# mcat-4cu-b-v2f.net
KiCad netlist of a schematic drawn in EAGLE
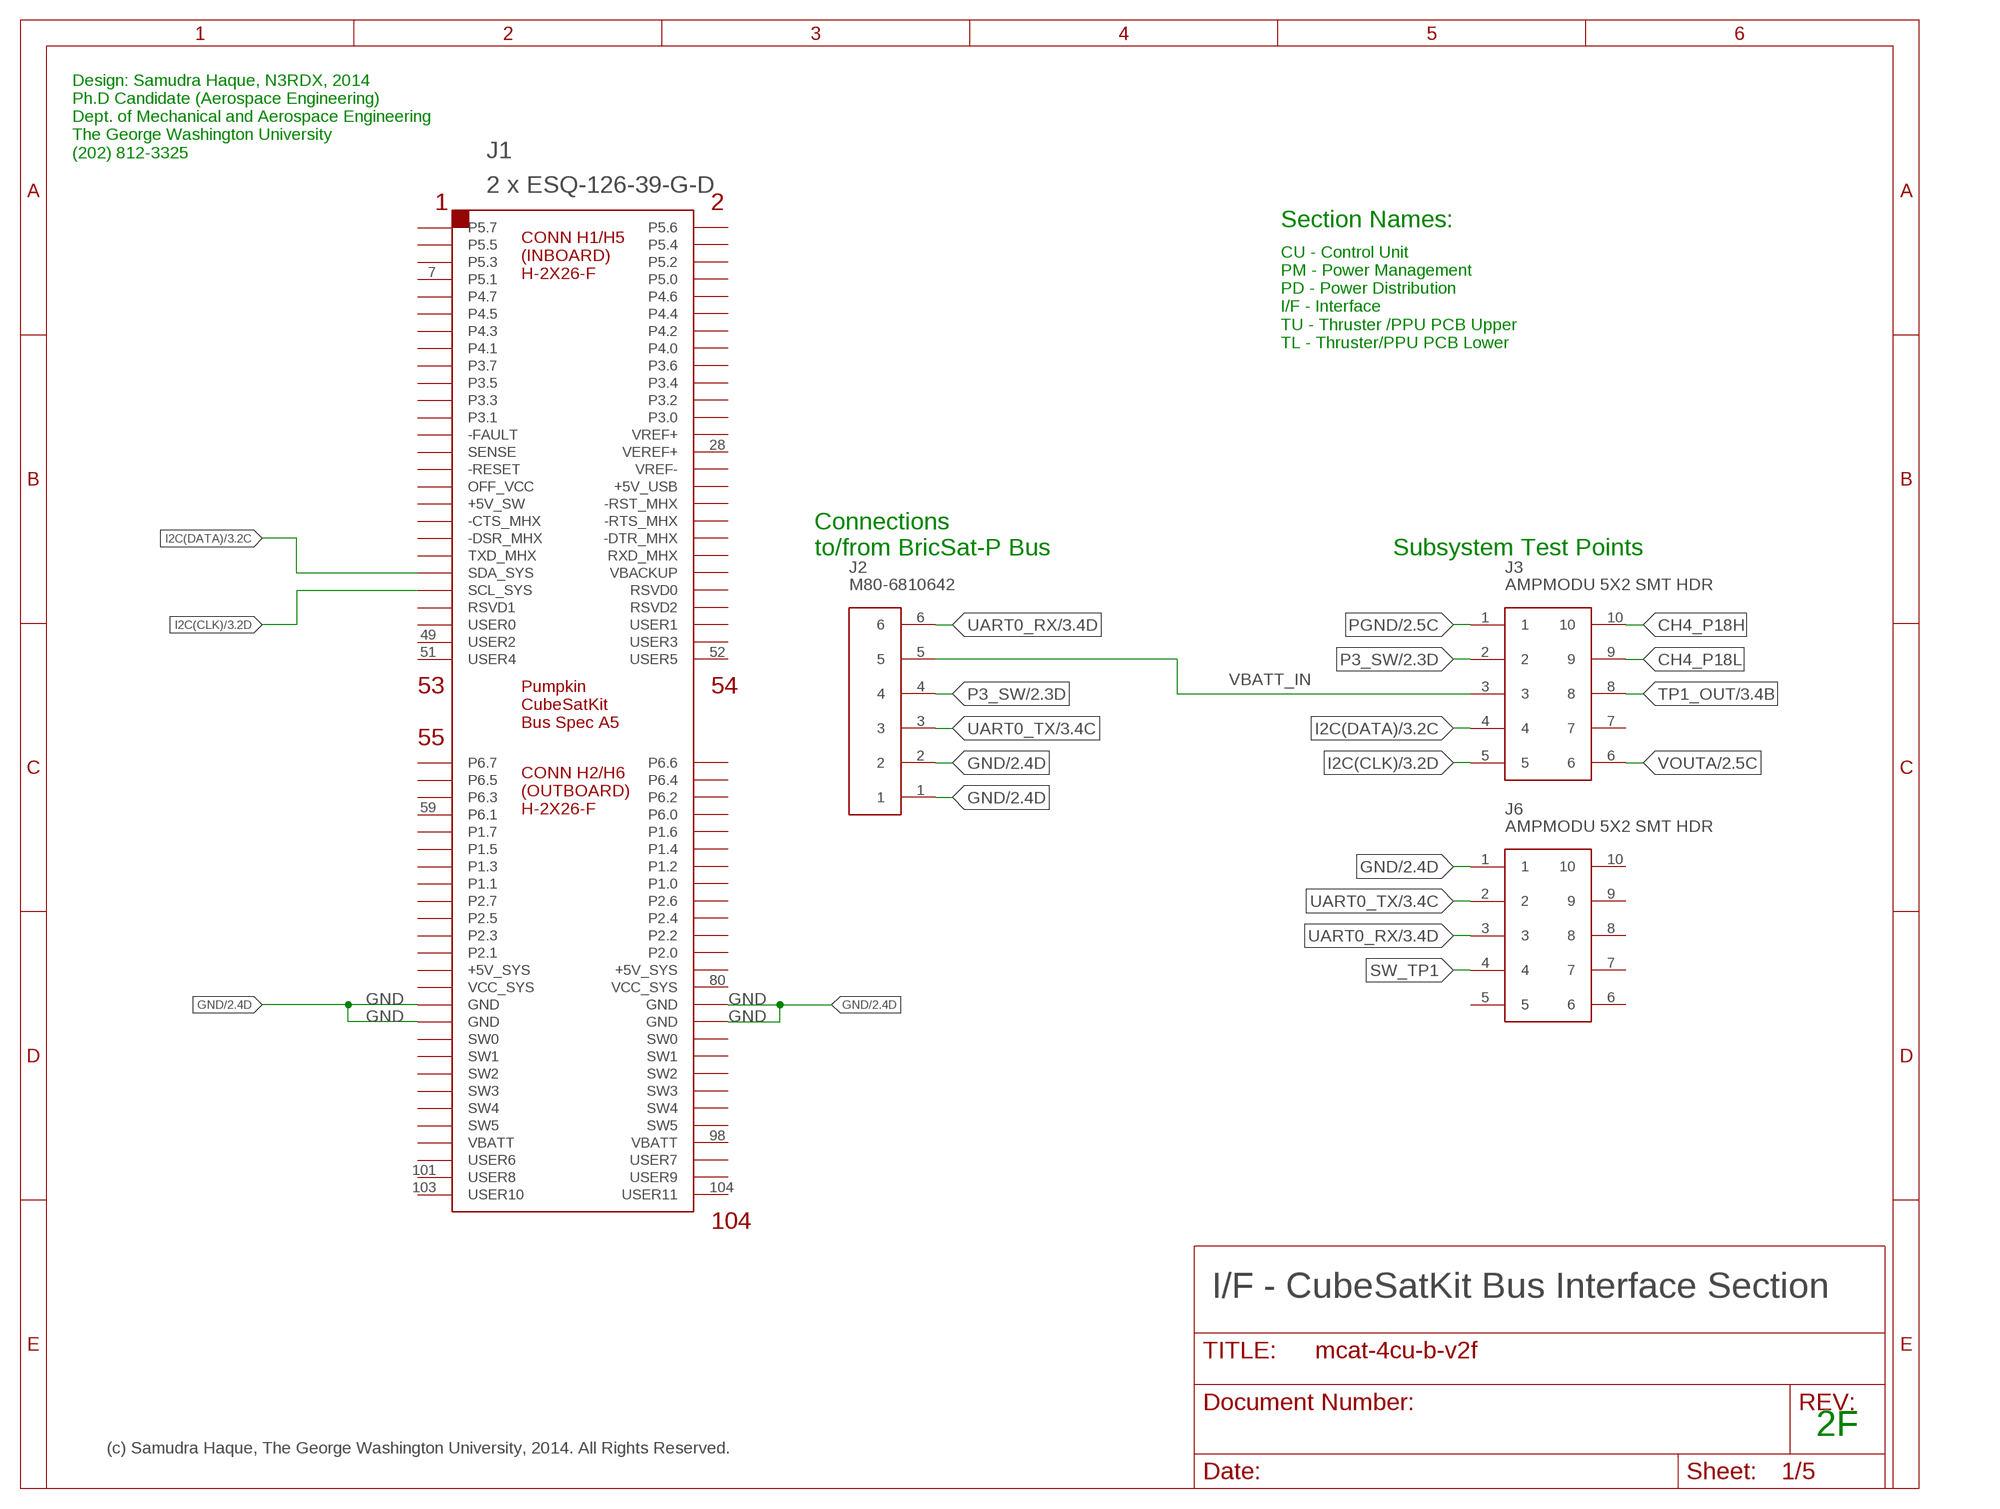
[diagram p0: schematic, sheet 1]
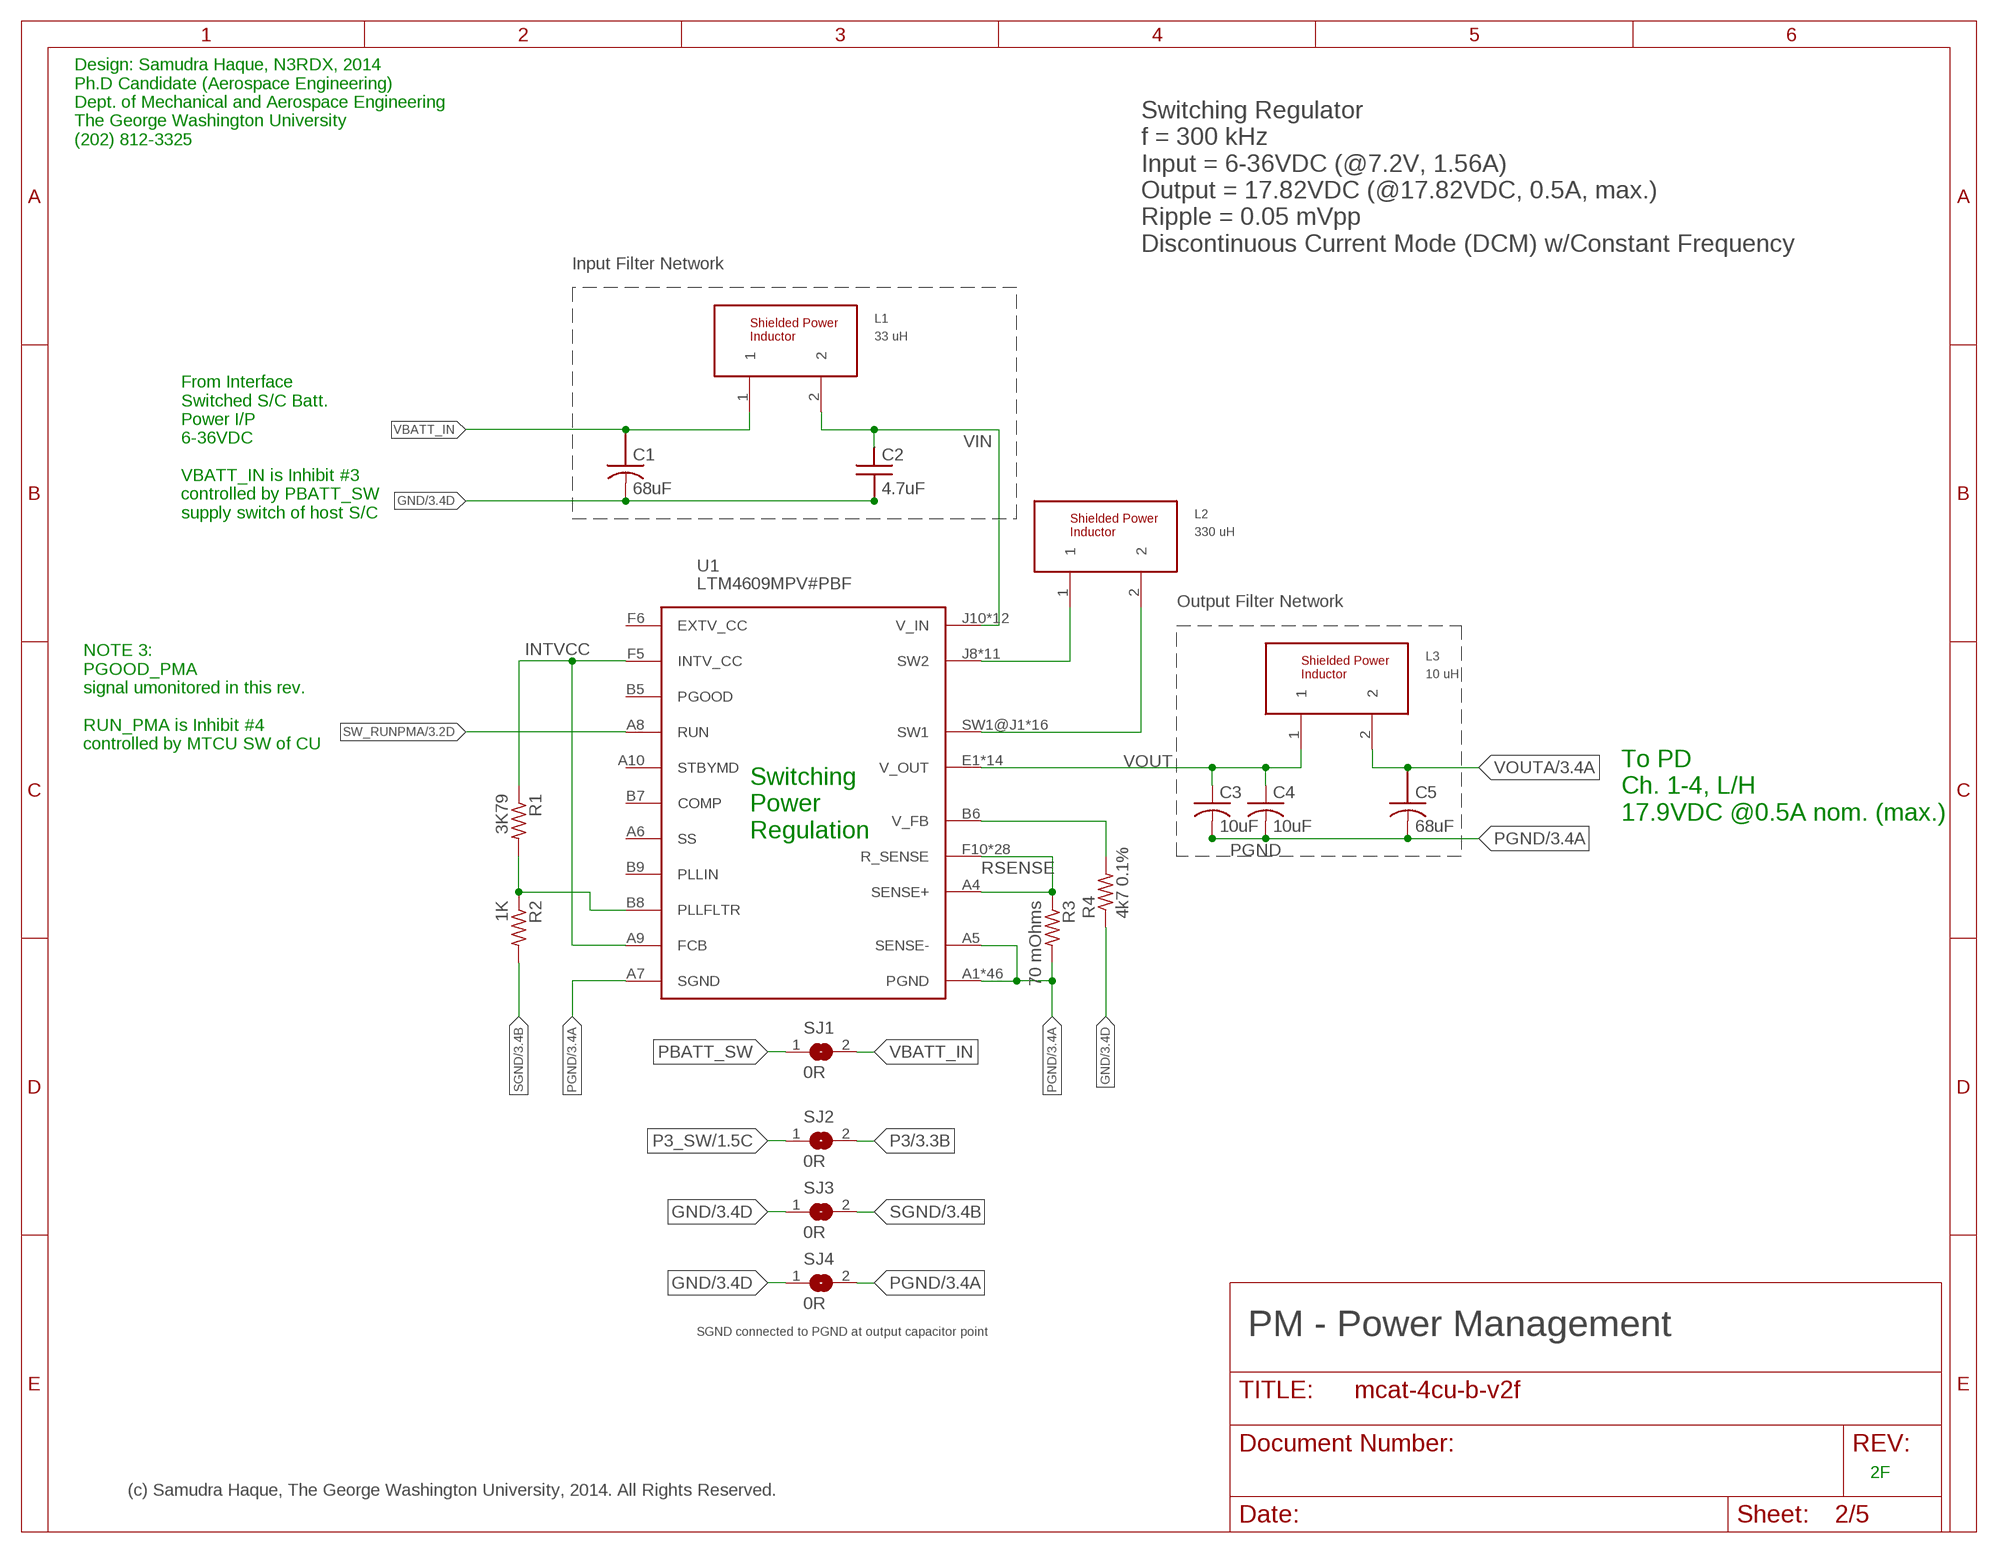
[diagram p1: schematic, sheet 2]
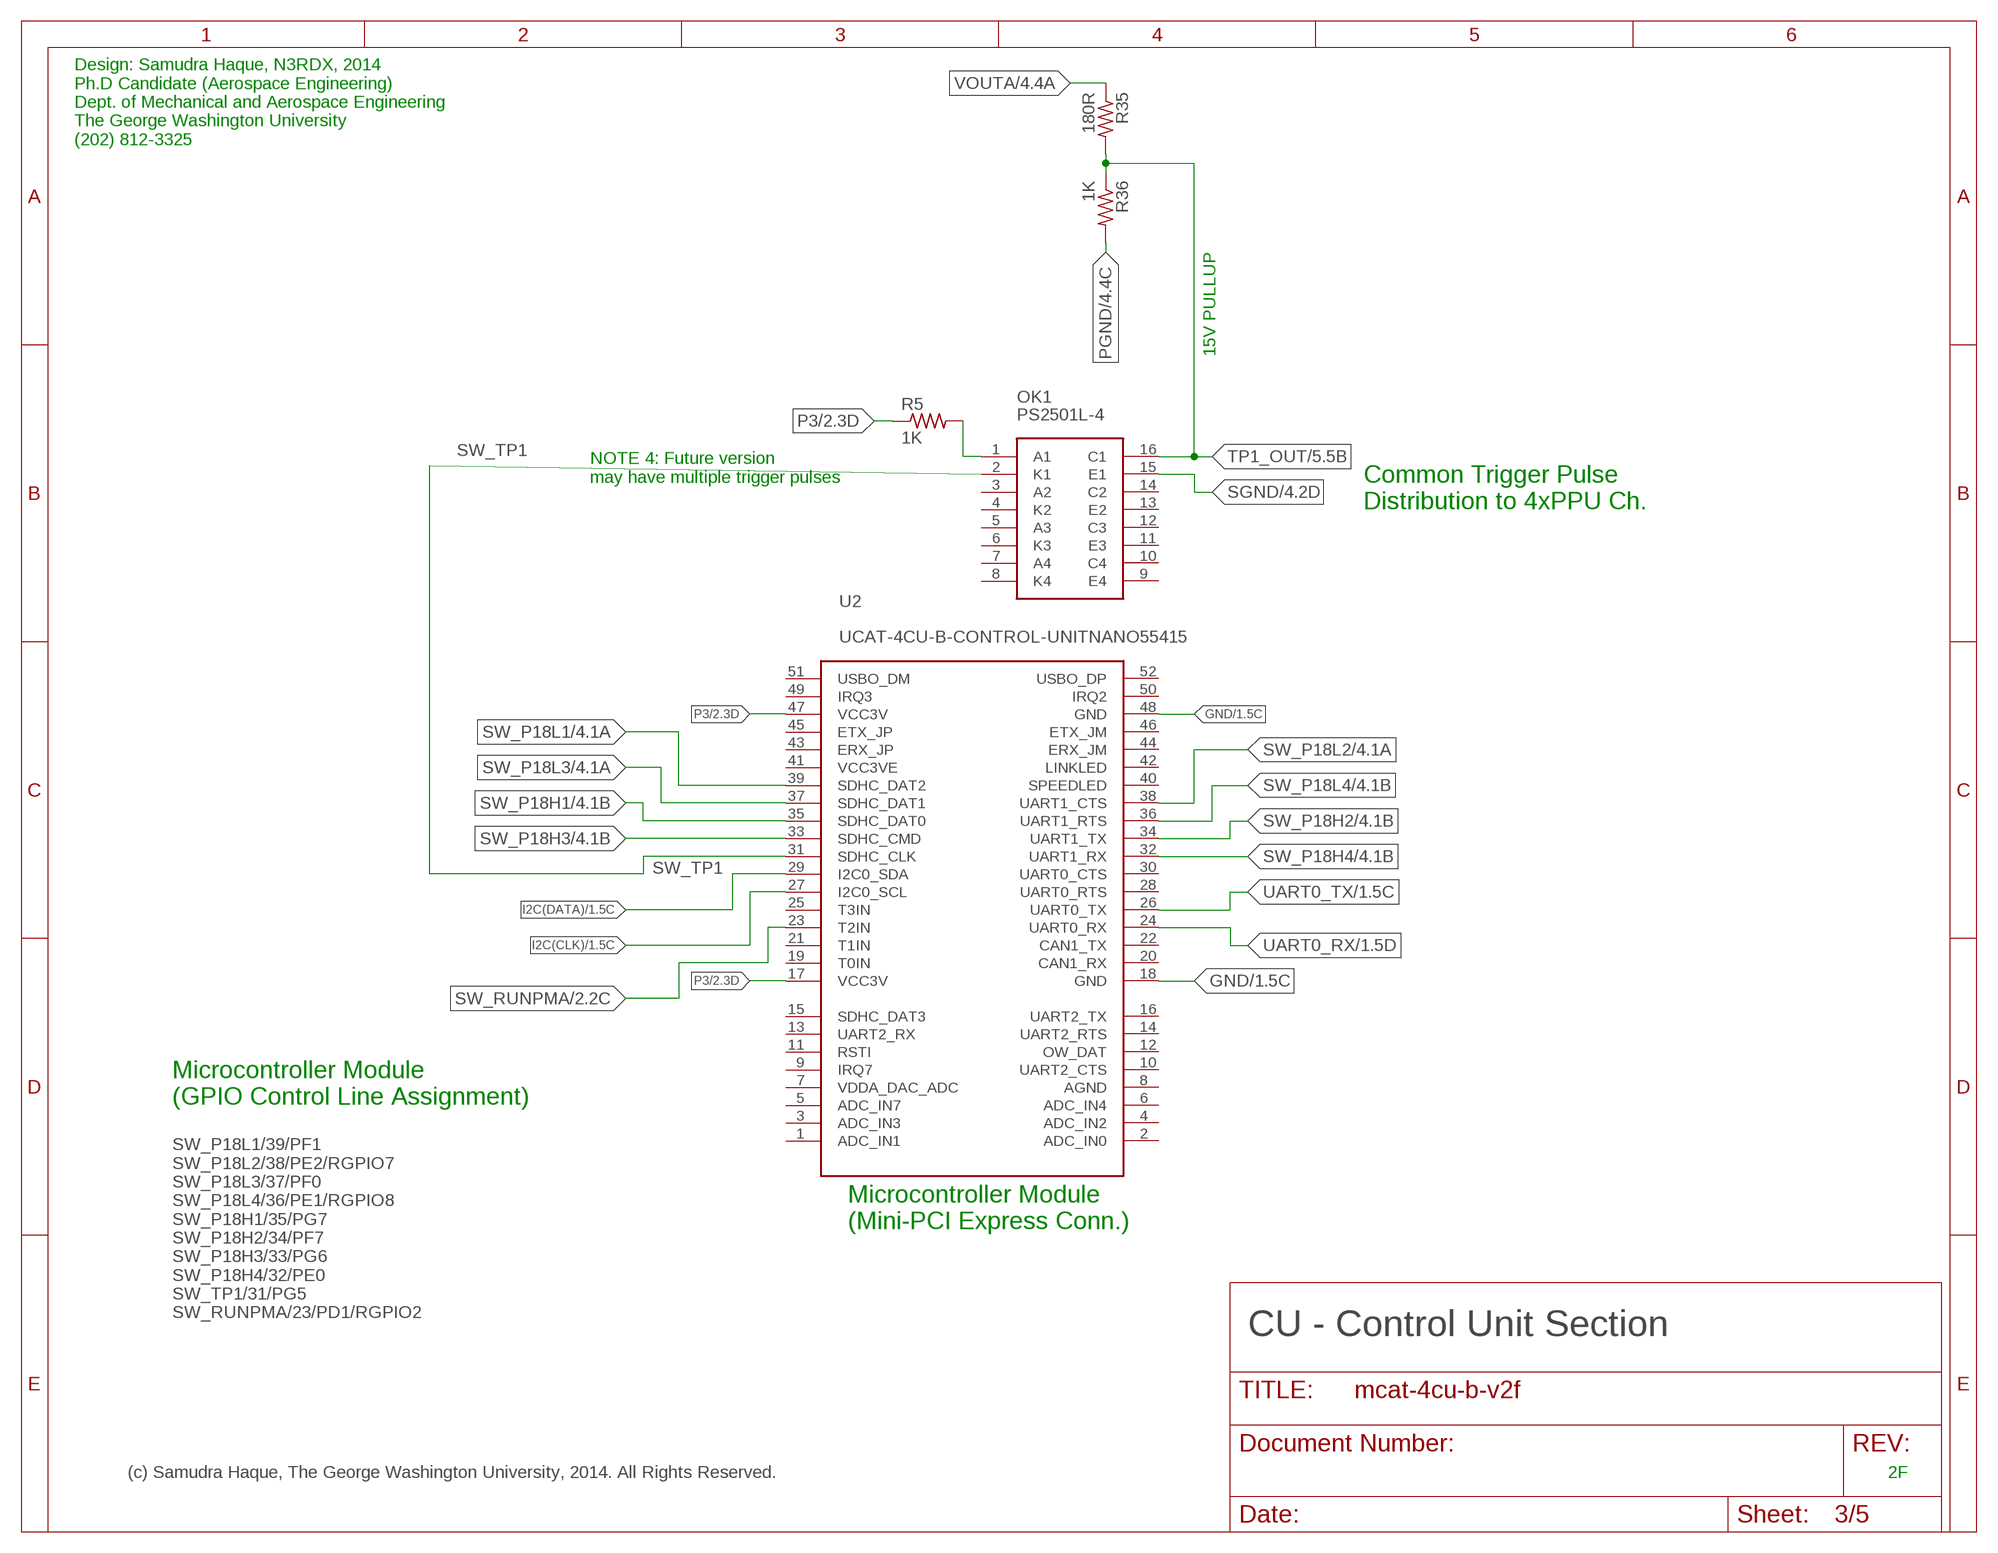
[diagram p2: schematic, sheet 3]
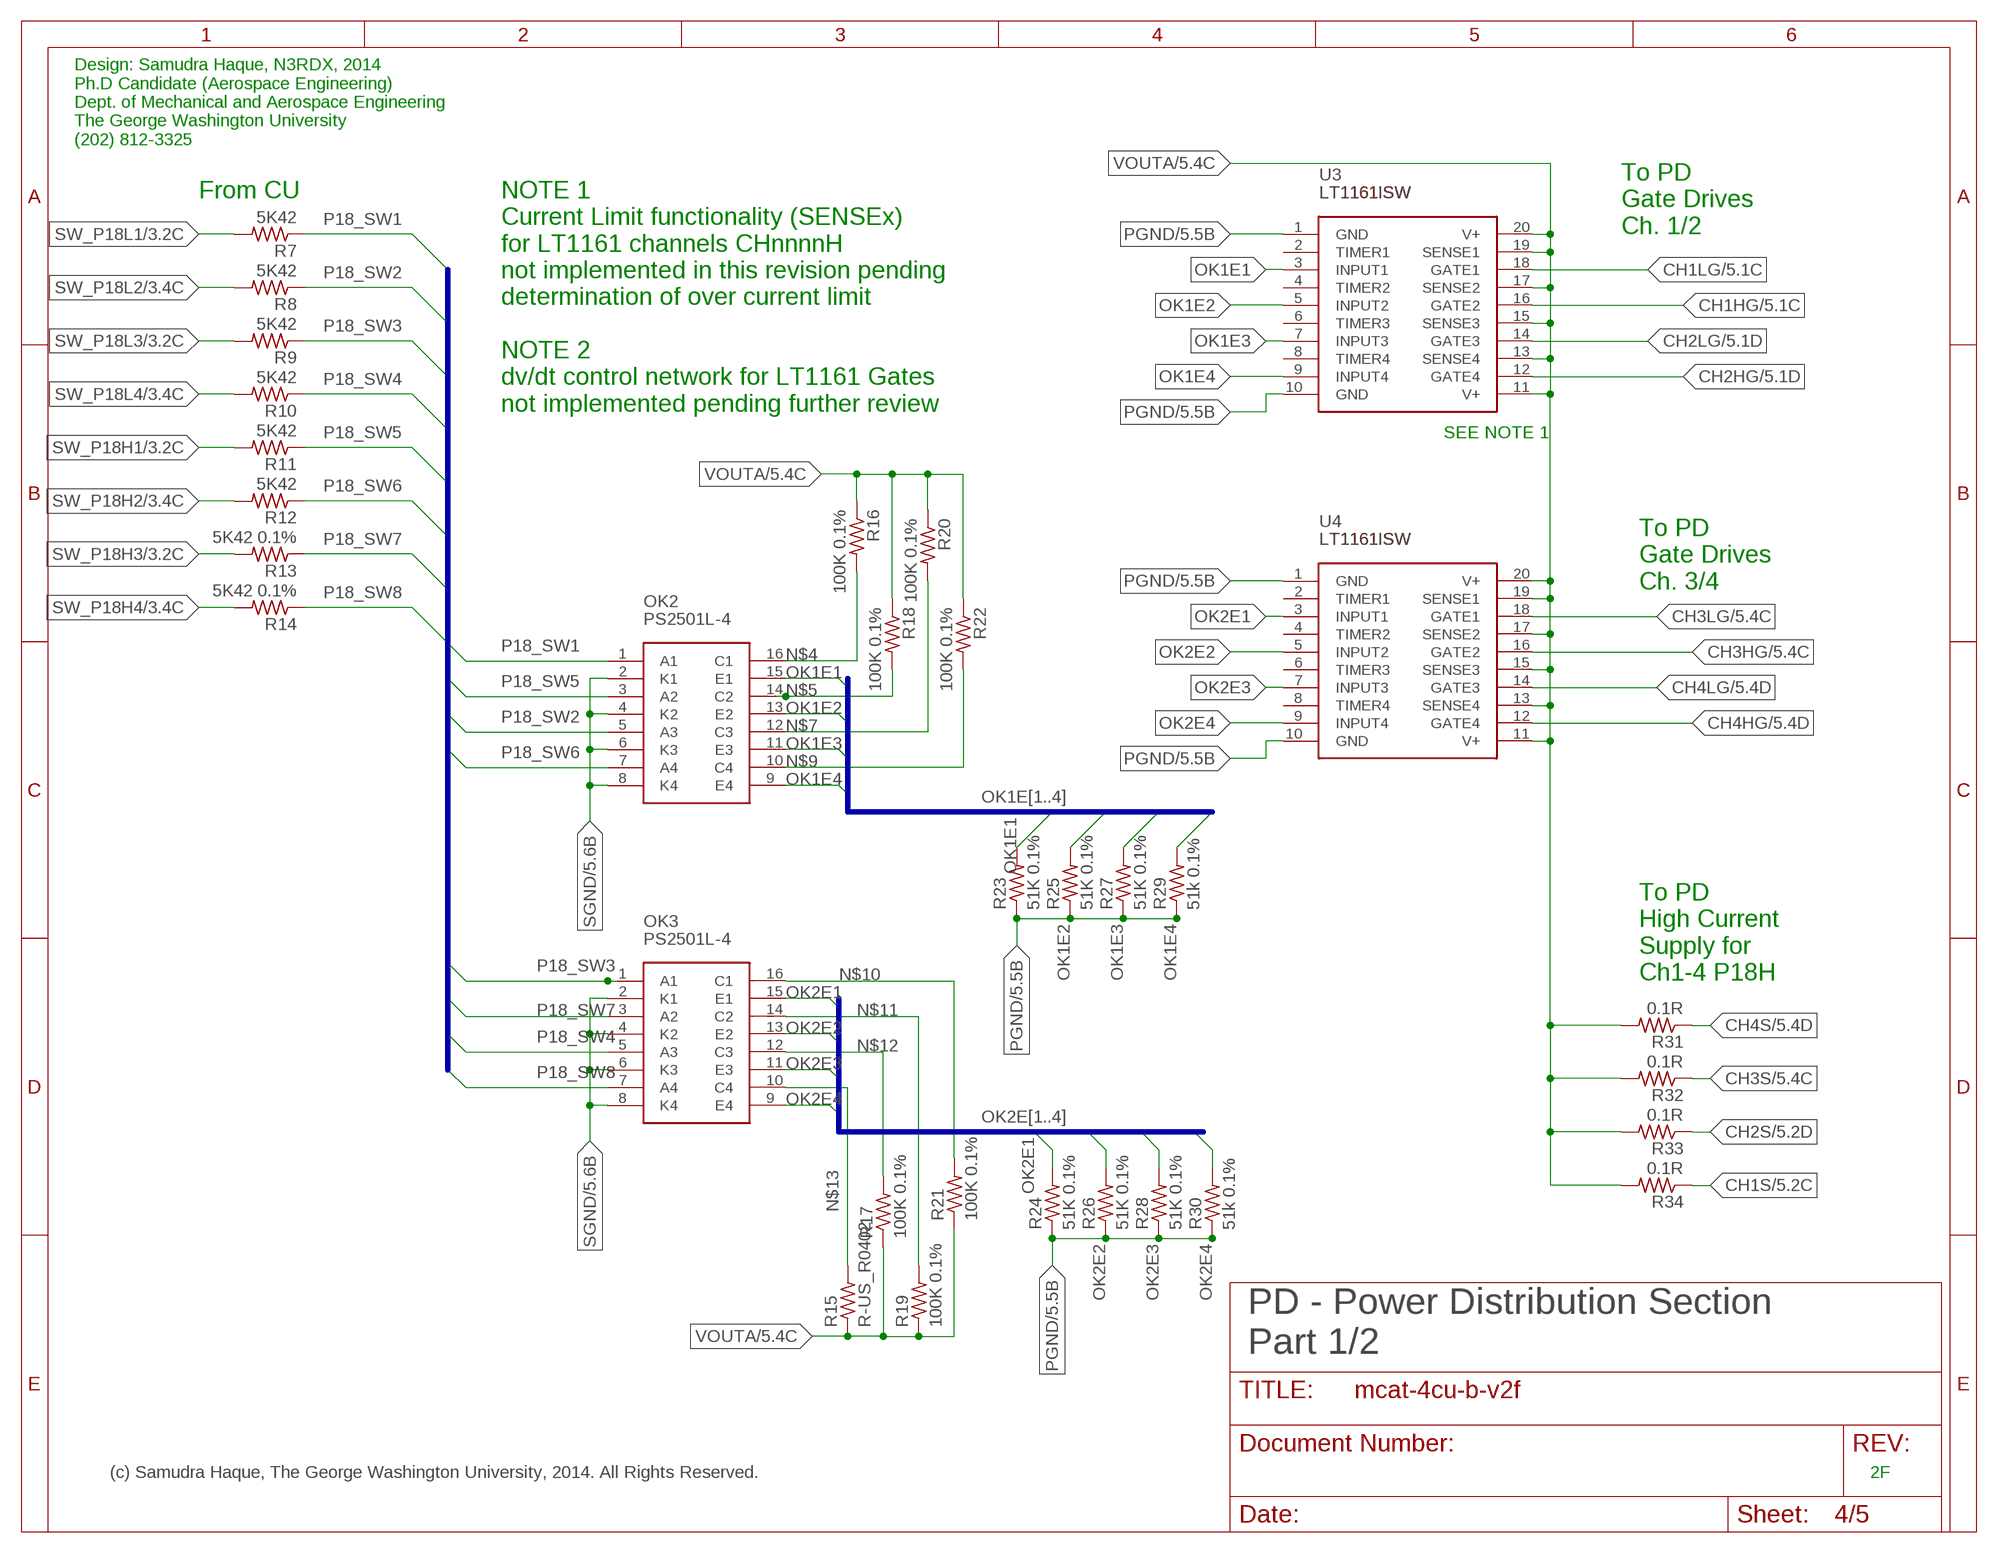
[diagram p3: schematic, sheet 4]
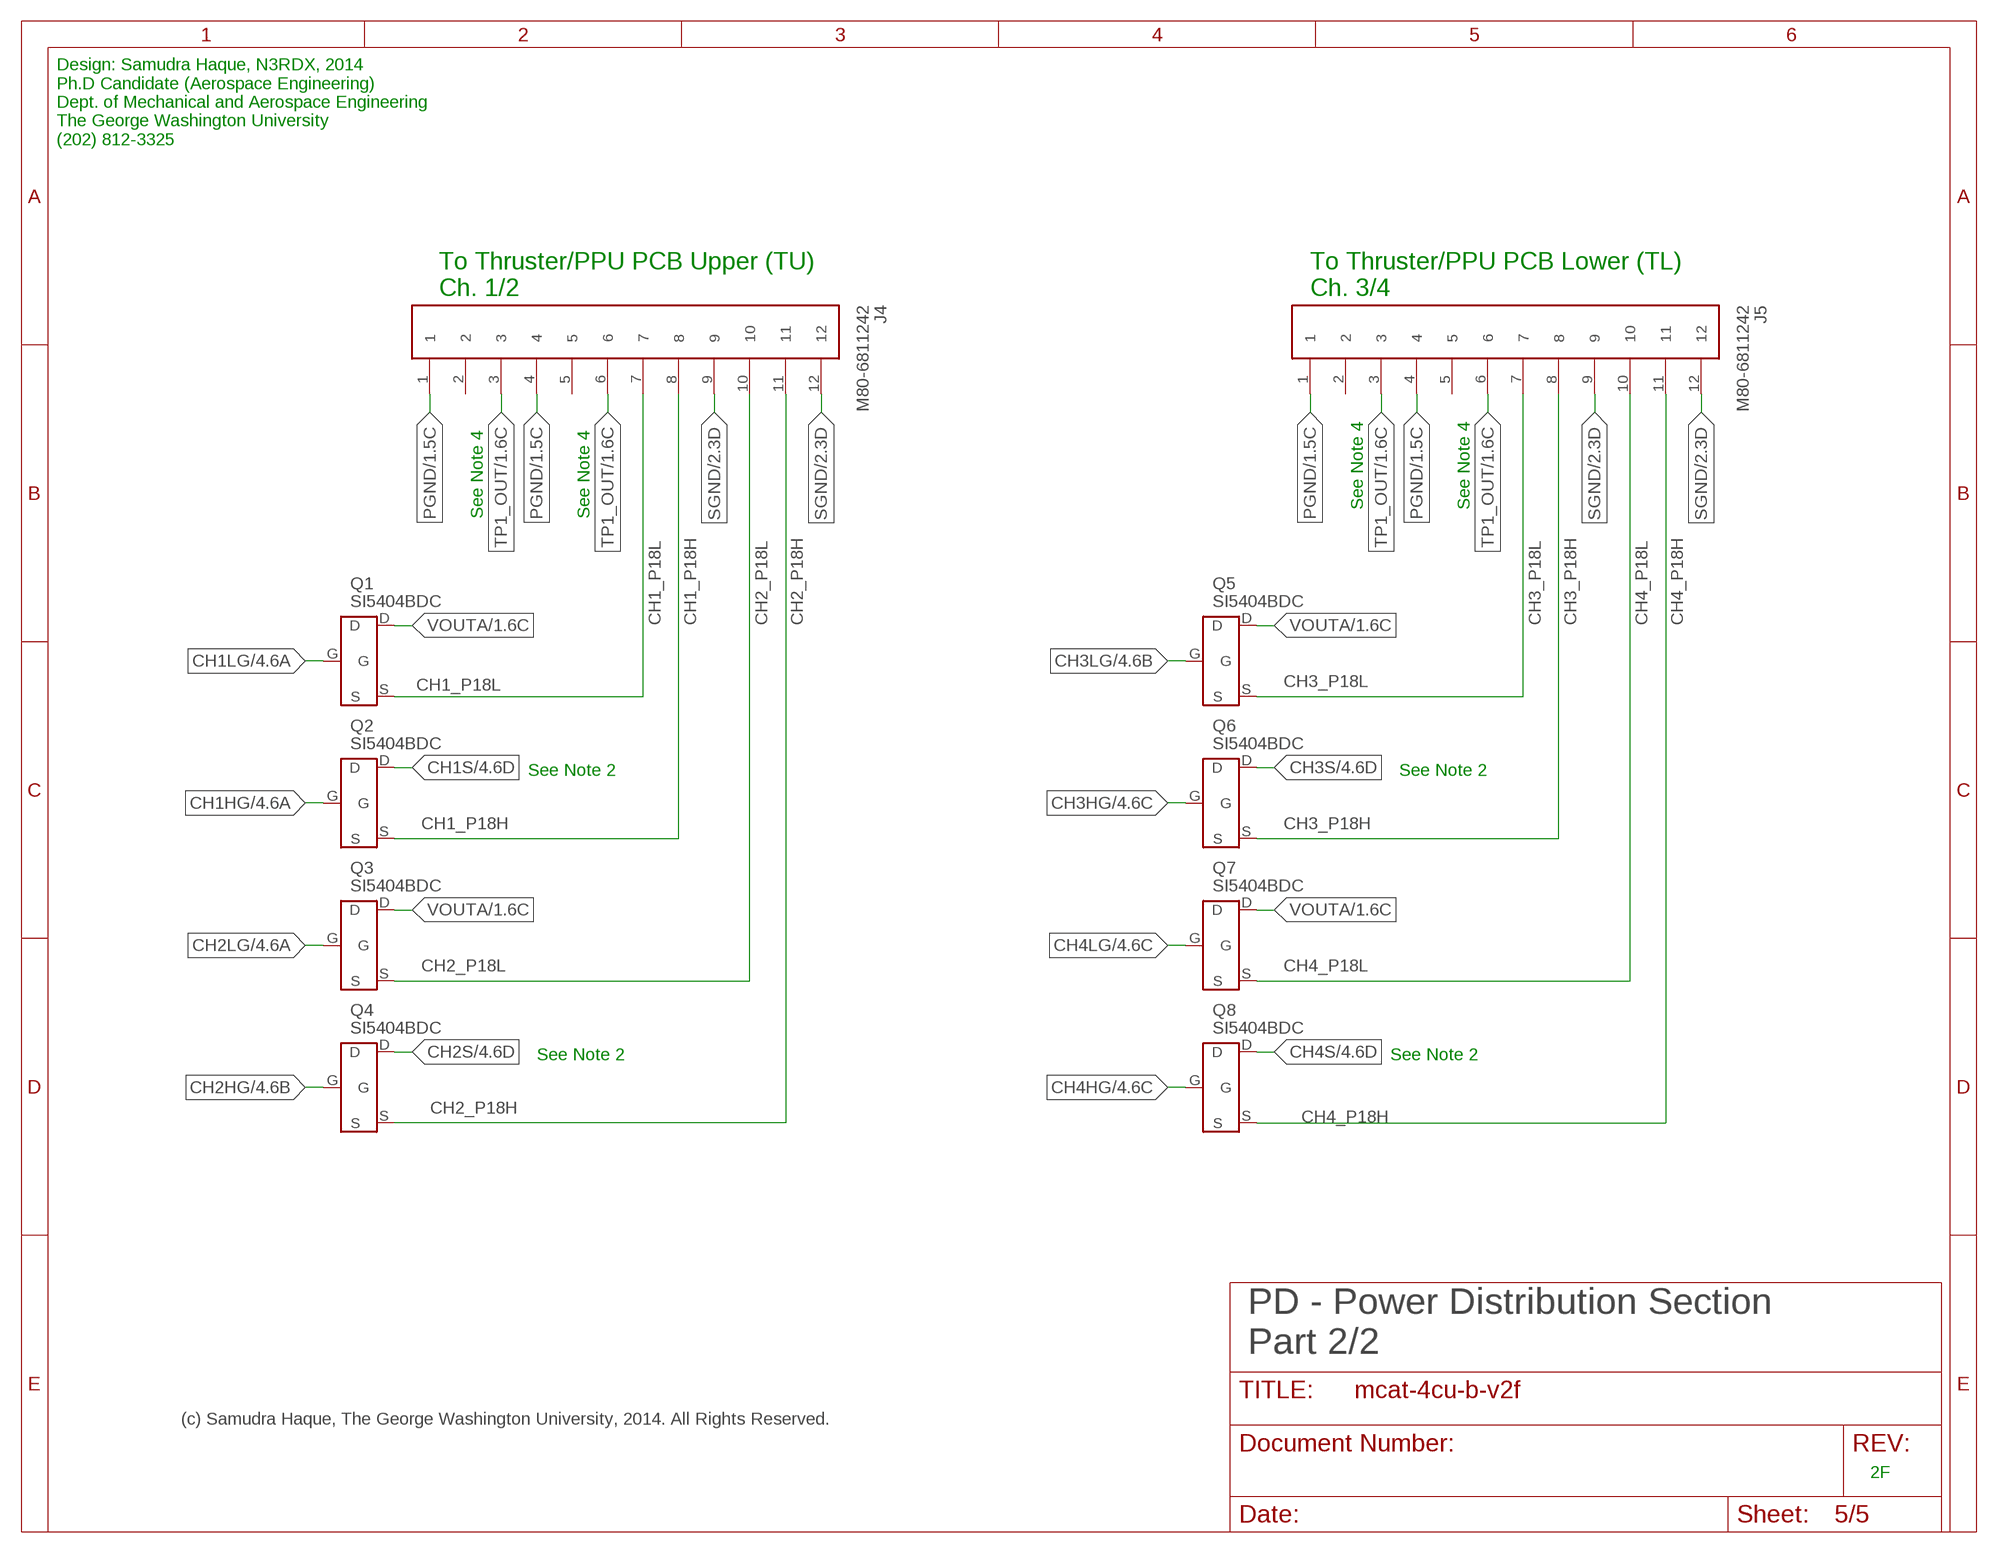
[diagram p4: schematic, sheet 5]

(export (version "E")
  (design (tool "Eeschema 10.0.6"))
  (components
    (comp (ref "J4")
      (value "M80-6811242")
      (footprint "eagle-import:M80-68112")
      (libsource (lib "eagle-import") (part "M80-6811242"))
    )
    (comp (ref "J5")
      (value "M80-6811242")
      (footprint "eagle-import:M80-68112")
      (libsource (lib "eagle-import") (part "M80-6811242"))
    )
    (comp (ref "Q1")
      (value "SI5404BDC")
      (footprint "eagle-import:1206-8-CHIPFET")
      (libsource (lib "eagle-import") (part "SI5404BDC"))
    )
    (comp (ref "Q2")
      (value "SI5404BDC")
      (footprint "eagle-import:1206-8-CHIPFET")
      (libsource (lib "eagle-import") (part "SI5404BDC"))
    )
    (comp (ref "Q3")
      (value "SI5404BDC")
      (footprint "eagle-import:1206-8-CHIPFET")
      (libsource (lib "eagle-import") (part "SI5404BDC"))
    )
    (comp (ref "Q4")
      (value "SI5404BDC")
      (footprint "eagle-import:1206-8-CHIPFET")
      (libsource (lib "eagle-import") (part "SI5404BDC"))
    )
    (comp (ref "Q5")
      (value "SI5404BDC")
      (footprint "eagle-import:1206-8-CHIPFET")
      (libsource (lib "eagle-import") (part "SI5404BDC"))
    )
    (comp (ref "Q6")
      (value "SI5404BDC")
      (footprint "eagle-import:1206-8-CHIPFET")
      (libsource (lib "eagle-import") (part "SI5404BDC"))
    )
    (comp (ref "Q7")
      (value "SI5404BDC")
      (footprint "eagle-import:1206-8-CHIPFET")
      (libsource (lib "eagle-import") (part "SI5404BDC"))
    )
    (comp (ref "Q8")
      (value "SI5404BDC")
      (footprint "eagle-import:1206-8-CHIPFET")
      (libsource (lib "eagle-import") (part "SI5404BDC"))
    )
    (comp (ref "C1")
      (value "68uF")
      (footprint "eagle-import:OS-CON-SVPF-F12")
      (libsource (lib "eagle-import") (part "OSCON-50SVPF68M"))
    )
    (comp (ref "C2")
      (value "4.7uF")
      (footprint "eagle-import:MLCC-X7R-1210")
      (libsource (lib "eagle-import") (part "AVX-LD105C475KAB2A"))
    )
    (comp (ref "C3")
      (value "10uF")
      (footprint "eagle-import:C1210K")
      (libsource (lib "eagle-import") (part "C-USC1210K"))
    )
    (comp (ref "C4")
      (value "10uF")
      (footprint "eagle-import:C1210K")
      (libsource (lib "eagle-import") (part "C-USC1210K"))
    )
    (comp (ref "C5")
      (value "68uF")
      (footprint "eagle-import:OS-CON-SVPF-F12")
      (libsource (lib "eagle-import") (part "OSCON-50SVPF68M"))
    )
    (comp (ref "L1")
      (value "33 uH")
      (footprint "eagle-import:MSS1048")
      (libsource (lib "eagle-import") (part "MSS1038-333ML_"))
    )
    (comp (ref "L2")
      (value "330 uH")
      (footprint "eagle-import:MSS1048")
      (libsource (lib "eagle-import") (part "MSS1048-334KL_"))
    )
    (comp (ref "L3")
      (value "10 uH")
      (footprint "eagle-import:SERIES-POWER-INDUCTORS")
      (fields (field (name "MF") "PANASONIC") (field (name "MPN") "ELL5PS100M"))
      (libsource (lib "eagle-import") (part "ELL-5PS100M"))
    )
    (comp (ref "R1")
      (value "3K79")
      (footprint "eagle-import:R0805")
      (libsource (lib "eagle-import") (part "R-US_R0805"))
    )
    (comp (ref "R2")
      (value "1K")
      (footprint "eagle-import:R0805")
      (libsource (lib "eagle-import") (part "R-US_R0805"))
    )
    (comp (ref "R3")
      (value "70 mOhms")
      (footprint "eagle-import:R1206")
      (libsource (lib "eagle-import") (part "resistor_R-US_R1206"))
    )
    (comp (ref "R4")
      (value "4k7 0.1%")
      (footprint "eagle-import:R0603")
      (libsource (lib "eagle-import") (part "resistor_R-US_R0603"))
    )
    (comp (ref "SJ1") (value "0R") (footprint "eagle-import:SJ") (libsource (lib "eagle-import") (part "SJ")))
    (comp (ref "SJ2") (value "0R") (footprint "eagle-import:SJ") (libsource (lib "eagle-import") (part "SJ")))
    (comp (ref "SJ3") (value "0R") (footprint "eagle-import:SJ") (libsource (lib "eagle-import") (part "SJ")))
    (comp (ref "SJ4") (value "0R") (footprint "eagle-import:SJ") (libsource (lib "eagle-import") (part "SJ")))
    (comp (ref "U1")
      (value "LTM4609MPV#PBF")
      (footprint "eagle-import:LGA-141-LTC-05-08-1840-B")
      (libsource (lib "eagle-import") (part "LTM4609MPV#PBFROHS/HITEMP"))
    )
    (comp (ref "J1")
      (value "2 x ESQ-126-39-G-D")
      (footprint "eagle-import:CSK-BUS-PKG")
      (libsource (lib "eagle-import") (part "CSK-BUS-CONN2X2X26"))
    )
    (comp (ref "J2")
      (value "M80-6810642")
      (footprint "eagle-import:M80-68106")
      (libsource (lib "eagle-import") (part "M80-6810642"))
    )
    (comp (ref "J3")
      (value "AMPMODU 5X2 SMT HDR")
      (footprint "eagle-import:AMPMODU-SMT-PIN-HEADER-5X2")
      (libsource (lib "eagle-import") (part "AMPMODU-5-146131-X(5X2)"))
    )
    (comp (ref "J6")
      (value "AMPMODU 5X2 SMT HDR")
      (footprint "eagle-import:AMPMODU-SMT-PIN-HEADER-5X2")
      (libsource (lib "eagle-import") (part "AMPMODU-5-146131-X(5X2)"))
    )
    (comp (ref "OK1")
      (value "PS2501L-4")
      (footprint "eagle-import:PS2501L-4")
      (libsource (lib "eagle-import") (part "PS2501L-4"))
    )
    (comp (ref "R5")
      (value "1K")
      (footprint "eagle-import:R0805")
      (libsource (lib "eagle-import") (part "resistor_R-US_R0805"))
    )
    (comp (ref "R35")
      (value "180R")
      (footprint "eagle-import:R0805")
      (libsource (lib "eagle-import") (part "resistor_R-US_R0805"))
    )
    (comp (ref "R36")
      (value "1K")
      (footprint "eagle-import:R0805")
      (libsource (lib "eagle-import") (part "resistor_R-US_R0805"))
    )
    (comp (ref "U2")
      (value "UCAT-4CU-B-CONTROL-UNITNANO55415")
      (footprint "eagle-import:MOLEX-MINI-PCI-EXPRESS-8MM-52CKT")
      (libsource (lib "eagle-import") (part "UCAT-4CU-B-CONTROL-UNITNANO55415"))
    )
    (comp (ref "OK2")
      (value "PS2501L-4")
      (footprint "eagle-import:PS2501L-4")
      (libsource (lib "eagle-import") (part "PS2501L-4"))
    )
    (comp (ref "OK3")
      (value "PS2501L-4")
      (footprint "eagle-import:PS2501L-4")
      (libsource (lib "eagle-import") (part "PS2501L-4"))
    )
    (comp (ref "R7")
      (value "5K42")
      (footprint "eagle-import:R1206")
      (libsource (lib "eagle-import") (part "resistor_R-US_R1206"))
    )
    (comp (ref "R8")
      (value "5K42")
      (footprint "eagle-import:R1206")
      (libsource (lib "eagle-import") (part "resistor_R-US_R1206"))
    )
    (comp (ref "R9")
      (value "5K42")
      (footprint "eagle-import:R1206")
      (libsource (lib "eagle-import") (part "resistor_R-US_R1206"))
    )
    (comp (ref "R10")
      (value "5K42")
      (footprint "eagle-import:R1206")
      (libsource (lib "eagle-import") (part "resistor_R-US_R1206"))
    )
    (comp (ref "R11")
      (value "5K42")
      (footprint "eagle-import:R1206")
      (libsource (lib "eagle-import") (part "resistor_R-US_R1206"))
    )
    (comp (ref "R12")
      (value "5K42")
      (footprint "eagle-import:R1206")
      (libsource (lib "eagle-import") (part "resistor_R-US_R1206"))
    )
    (comp (ref "R13")
      (value "5K42 0.1%")
      (footprint "eagle-import:R1206")
      (libsource (lib "eagle-import") (part "resistor_R-US_R1206"))
    )
    (comp (ref "R14")
      (value "5K42 0.1%")
      (footprint "eagle-import:R1206")
      (libsource (lib "eagle-import") (part "resistor_R-US_R1206"))
    )
    (comp (ref "R15")
      (value "R-US_R0402")
      (footprint "eagle-import:R0402")
      (libsource (lib "eagle-import") (part "resistor_R-US_R0402"))
    )
    (comp (ref "R16")
      (value "100K 0.1%")
      (footprint "eagle-import:R0402")
      (libsource (lib "eagle-import") (part "resistor_R-US_R0402"))
    )
    (comp (ref "R17")
      (value "100K 0.1%")
      (footprint "eagle-import:R0402")
      (libsource (lib "eagle-import") (part "resistor_R-US_R0402"))
    )
    (comp (ref "R18")
      (value "100K 0.1%")
      (footprint "eagle-import:R0402")
      (libsource (lib "eagle-import") (part "resistor_R-US_R0402"))
    )
    (comp (ref "R19")
      (value "100K 0.1%")
      (footprint "eagle-import:R0402")
      (libsource (lib "eagle-import") (part "resistor_R-US_R0402"))
    )
    (comp (ref "R20")
      (value "100K 0.1%")
      (footprint "eagle-import:R0402")
      (libsource (lib "eagle-import") (part "resistor_R-US_R0402"))
    )
    (comp (ref "R21")
      (value "100K 0.1%")
      (footprint "eagle-import:R0402")
      (libsource (lib "eagle-import") (part "resistor_R-US_R0402"))
    )
    (comp (ref "R22")
      (value "100K 0.1%")
      (footprint "eagle-import:R0402")
      (libsource (lib "eagle-import") (part "resistor_R-US_R0402"))
    )
    (comp (ref "R23")
      (value "51K 0.1%")
      (footprint "eagle-import:R0603")
      (libsource (lib "eagle-import") (part "resistor_R-US_R0603"))
    )
    (comp (ref "R24")
      (value "51K 0.1%")
      (footprint "eagle-import:R0603")
      (libsource (lib "eagle-import") (part "resistor_R-US_R0603"))
    )
    (comp (ref "R25")
      (value "51K 0.1%")
      (footprint "eagle-import:R0603")
      (libsource (lib "eagle-import") (part "resistor_R-US_R0603"))
    )
    (comp (ref "R26")
      (value "51K 0.1%")
      (footprint "eagle-import:R0603")
      (libsource (lib "eagle-import") (part "resistor_R-US_R0603"))
    )
    (comp (ref "R27")
      (value "51K 0.1%")
      (footprint "eagle-import:R0603")
      (libsource (lib "eagle-import") (part "resistor_R-US_R0603"))
    )
    (comp (ref "R28")
      (value "51K 0.1%")
      (footprint "eagle-import:R0603")
      (libsource (lib "eagle-import") (part "resistor_R-US_R0603"))
    )
    (comp (ref "R29")
      (value "51k 0.1%")
      (footprint "eagle-import:R0603")
      (libsource (lib "eagle-import") (part "resistor_R-US_R0603"))
    )
    (comp (ref "R30")
      (value "51k 0.1%")
      (footprint "eagle-import:R0603")
      (libsource (lib "eagle-import") (part "resistor_R-US_R0603"))
    )
    (comp (ref "R31")
      (value "0.1R")
      (footprint "eagle-import:R0402")
      (libsource (lib "eagle-import") (part "R-US_R0402"))
    )
    (comp (ref "R32")
      (value "0.1R")
      (footprint "eagle-import:R0402")
      (libsource (lib "eagle-import") (part "R-US_R0402"))
    )
    (comp (ref "R33")
      (value "0.1R")
      (footprint "eagle-import:R0402")
      (libsource (lib "eagle-import") (part "R-US_R0402"))
    )
    (comp (ref "R34")
      (value "0.1R")
      (footprint "eagle-import:R0402")
      (libsource (lib "eagle-import") (part "R-US_R0402"))
    )
    (comp (ref "U3")
      (value "LT1161ISW")
      (footprint "eagle-import:20-LEAD-PLASTIC-SO")
      (libsource (lib "eagle-import") (part "LT1161ISW"))
    )
    (comp (ref "U4")
      (value "LT1161ISW")
      (footprint "eagle-import:20-LEAD-PLASTIC-SO")
      (libsource (lib "eagle-import") (part "LT1161ISW"))
    )
  )
  (nets
    (net (code "3") (name "CH1HG") (class "Default")
      (node (ref "Q2") (pin "G") (pinfunction "G_G") (pintype "bidirectional"))
      (node (ref "U3") (pin "16") (pinfunction "GATE2_16") (pintype "bidirectional"))
    )
    (net (code "4") (name "CH1LG") (class "Default")
      (node (ref "Q1") (pin "G") (pinfunction "G_G") (pintype "bidirectional"))
      (node (ref "U3") (pin "18") (pinfunction "GATE1_18") (pintype "bidirectional"))
    )
    (net (code "5") (name "CH1S") (class "Default")
      (node (ref "Q2") (pin "D") (pinfunction "D_D") (pintype "bidirectional"))
      (node (ref "R34") (pin "1") (pinfunction "1_1") (pintype "passive"))
    )
    (net (code "6") (name "CH1_P18H") (class "Default")
      (node (ref "J4") (pin "8") (pinfunction "8_8") (pintype "bidirectional"))
      (node (ref "Q2") (pin "S") (pinfunction "S_S") (pintype "bidirectional"))
    )
    (net (code "7") (name "CH1_P18L") (class "Default")
      (node (ref "J4") (pin "7") (pinfunction "7_7") (pintype "bidirectional"))
      (node (ref "Q1") (pin "S") (pinfunction "S_S") (pintype "bidirectional"))
    )
    (net (code "8") (name "CH2HG") (class "Default")
      (node (ref "Q4") (pin "G") (pinfunction "G_G") (pintype "bidirectional"))
      (node (ref "U3") (pin "12") (pinfunction "GATE4_12") (pintype "bidirectional"))
    )
    (net (code "9") (name "CH2LG") (class "Default")
      (node (ref "Q3") (pin "G") (pinfunction "G_G") (pintype "bidirectional"))
      (node (ref "U3") (pin "14") (pinfunction "GATE3_14") (pintype "bidirectional"))
    )
    (net (code "10") (name "CH2S") (class "Default")
      (node (ref "Q4") (pin "D") (pinfunction "D_D") (pintype "bidirectional"))
      (node (ref "R33") (pin "1") (pinfunction "1_1") (pintype "passive"))
    )
    (net (code "11") (name "CH2_P18H") (class "Default")
      (node (ref "J4") (pin "11") (pinfunction "11_11") (pintype "bidirectional"))
      (node (ref "Q4") (pin "S") (pinfunction "S_S") (pintype "bidirectional"))
    )
    (net (code "12") (name "CH2_P18L") (class "Default")
      (node (ref "J4") (pin "10") (pinfunction "10_10") (pintype "bidirectional"))
      (node (ref "Q3") (pin "S") (pinfunction "S_S") (pintype "bidirectional"))
    )
    (net (code "13") (name "CH3HG") (class "Default")
      (node (ref "Q6") (pin "G") (pinfunction "G_G") (pintype "bidirectional"))
      (node (ref "U4") (pin "16") (pinfunction "GATE2_16") (pintype "bidirectional"))
    )
    (net (code "14") (name "CH3LG") (class "Default")
      (node (ref "Q5") (pin "G") (pinfunction "G_G") (pintype "bidirectional"))
      (node (ref "U4") (pin "18") (pinfunction "GATE1_18") (pintype "bidirectional"))
    )
    (net (code "15") (name "CH3S") (class "Default")
      (node (ref "Q6") (pin "D") (pinfunction "D_D") (pintype "bidirectional"))
      (node (ref "R32") (pin "1") (pinfunction "1_1") (pintype "passive"))
    )
    (net (code "16") (name "CH3_P18H") (class "Default")
      (node (ref "J5") (pin "8") (pinfunction "8_8") (pintype "bidirectional"))
      (node (ref "Q6") (pin "S") (pinfunction "S_S") (pintype "bidirectional"))
    )
    (net (code "17") (name "CH3_P18L") (class "Default")
      (node (ref "J5") (pin "7") (pinfunction "7_7") (pintype "bidirectional"))
      (node (ref "Q5") (pin "S") (pinfunction "S_S") (pintype "bidirectional"))
    )
    (net (code "18") (name "CH4HG") (class "Default")
      (node (ref "Q8") (pin "G") (pinfunction "G_G") (pintype "bidirectional"))
      (node (ref "U4") (pin "12") (pinfunction "GATE4_12") (pintype "bidirectional"))
    )
    (net (code "19") (name "CH4LG") (class "Default")
      (node (ref "Q7") (pin "G") (pinfunction "G_G") (pintype "bidirectional"))
      (node (ref "U4") (pin "14") (pinfunction "GATE3_14") (pintype "bidirectional"))
    )
    (net (code "20") (name "CH4S") (class "Default")
      (node (ref "Q8") (pin "D") (pinfunction "D_D") (pintype "bidirectional"))
      (node (ref "R31") (pin "1") (pinfunction "1_1") (pintype "passive"))
    )
    (net (code "21") (name "CH4_P18H") (class "Default")
      (node (ref "J3") (pin "10") (pinfunction "10_10") (pintype "bidirectional"))
      (node (ref "J5") (pin "11") (pinfunction "11_11") (pintype "bidirectional"))
      (node (ref "Q8") (pin "S") (pinfunction "S_S") (pintype "bidirectional"))
    )
    (net (code "22") (name "CH4_P18L") (class "Default")
      (node (ref "J3") (pin "9") (pinfunction "9_9") (pintype "bidirectional"))
      (node (ref "J5") (pin "10") (pinfunction "10_10") (pintype "bidirectional"))
      (node (ref "Q7") (pin "S") (pinfunction "S_S") (pintype "bidirectional"))
    )
    (net (code "23") (name "GND") (class "Default")
      (node (ref "C1") (pin "K1") (pinfunction "K_K1") (pintype "passive"))
      (node (ref "C2") (pin "2") (pinfunction "2_2") (pintype "passive"))
      (node (ref "J1") (pin "81") (pinfunction "GND_81") (pintype "bidirectional"))
      (node (ref "J1") (pin "82") (pinfunction "GND_82") (pintype "bidirectional"))
      (node (ref "J1") (pin "83") (pinfunction "GND_83") (pintype "bidirectional"))
      (node (ref "J1") (pin "84") (pinfunction "GND_84") (pintype "bidirectional"))
      (node (ref "J2") (pin "1") (pinfunction "1_1") (pintype "bidirectional"))
      (node (ref "J2") (pin "2") (pinfunction "2_2") (pintype "bidirectional"))
      (node (ref "J6") (pin "1") (pinfunction "1_1") (pintype "bidirectional"))
      (node (ref "R4") (pin "1") (pinfunction "1_1") (pintype "passive"))
      (node (ref "SJ3") (pin "1") (pinfunction "1_1") (pintype "passive"))
      (node (ref "SJ4") (pin "1") (pinfunction "1_1") (pintype "passive"))
      (node (ref "U2") (pin "18") (pinfunction "GND_18") (pintype "bidirectional"))
      (node (ref "U2") (pin "48") (pinfunction "GND_48") (pintype "bidirectional"))
    )
    (net (code "24") (name "I2C(CLK)") (class "Default")
      (node (ref "J1") (pin "43") (pinfunction "SCL_SYS_43") (pintype "bidirectional"))
      (node (ref "J3") (pin "5") (pinfunction "5_5") (pintype "bidirectional"))
      (node (ref "U2") (pin "27") (pinfunction "I2C0_SCL_27") (pintype "bidirectional"))
    )
    (net (code "25") (name "I2C(DATA)") (class "Default")
      (node (ref "J1") (pin "41") (pinfunction "SDA_SYS_41") (pintype "bidirectional"))
      (node (ref "J3") (pin "4") (pinfunction "4_4") (pintype "bidirectional"))
      (node (ref "U2") (pin "29") (pinfunction "I2C0_SDA_29") (pintype "bidirectional"))
    )
    (net (code "26") (name "INTVCC") (class "Default")
      (node (ref "R1") (pin "1") (pinfunction "1_1") (pintype "passive"))
      (node (ref "U1") (pin "A9") (pinfunction "FCB_A9") (pintype "bidirectional"))
      (node (ref "U1") (pin "F5") (pinfunction "INTV_CC_F5") (pintype "bidirectional"))
    )
    (net (code "27") (name "N$4") (class "Default")
      (node (ref "OK2") (pin "16") (pinfunction "C1_16") (pintype "bidirectional"))
      (node (ref "R16") (pin "2") (pinfunction "2_2") (pintype "passive"))
    )
    (net (code "28") (name "N$5") (class "Default")
      (node (ref "OK2") (pin "14") (pinfunction "C2_14") (pintype "bidirectional"))
      (node (ref "R18") (pin "2") (pinfunction "2_2") (pintype "passive"))
    )
    (net (code "29") (name "N$7") (class "Default")
      (node (ref "OK2") (pin "12") (pinfunction "C3_12") (pintype "bidirectional"))
      (node (ref "R20") (pin "2") (pinfunction "2_2") (pintype "passive"))
    )
    (net (code "30") (name "N$9") (class "Default")
      (node (ref "OK2") (pin "10") (pinfunction "C4_10") (pintype "bidirectional"))
      (node (ref "R22") (pin "2") (pinfunction "2_2") (pintype "passive"))
    )
    (net (code "31") (name "N$10") (class "Default")
      (node (ref "OK3") (pin "16") (pinfunction "C1_16") (pintype "bidirectional"))
      (node (ref "R21") (pin "2") (pinfunction "2_2") (pintype "passive"))
    )
    (net (code "32") (name "N$11") (class "Default")
      (node (ref "OK3") (pin "14") (pinfunction "C2_14") (pintype "bidirectional"))
      (node (ref "R19") (pin "2") (pinfunction "2_2") (pintype "passive"))
    )
    (net (code "33") (name "N$12") (class "Default")
      (node (ref "OK3") (pin "12") (pinfunction "C3_12") (pintype "bidirectional"))
      (node (ref "R17") (pin "2") (pinfunction "2_2") (pintype "passive"))
    )
    (net (code "34") (name "N$13") (class "Default")
      (node (ref "OK3") (pin "10") (pinfunction "C4_10") (pintype "bidirectional"))
      (node (ref "R15") (pin "2") (pinfunction "2_2") (pintype "passive"))
    )
    (net (code "35") (name "Net-(L2-Pad1)") (class "Default")
      (node (ref "L2") (pin "1") (pinfunction "1_1") (pintype "bidirectional"))
      (node (ref "U1") (pin "J8") (pinfunction "SW2_J8") (pintype "bidirectional"))
      (node (ref "U1") (pin "J9") (pinfunction "SW2_J9") (pintype "bidirectional"))
      (node (ref "U1") (pin "K7") (pinfunction "SW2_K7") (pintype "bidirectional"))
      (node (ref "U1") (pin "K8") (pinfunction "SW2_K8") (pintype "bidirectional"))
      (node (ref "U1") (pin "K9") (pinfunction "SW2_K9") (pintype "bidirectional"))
      (node (ref "U1") (pin "L7") (pinfunction "SW2_L7") (pintype "bidirectional"))
      (node (ref "U1") (pin "L8") (pinfunction "SW2_L8") (pintype "bidirectional"))
      (node (ref "U1") (pin "L9") (pinfunction "SW2_L9") (pintype "bidirectional"))
      (node (ref "U1") (pin "M7") (pinfunction "SW2_M7") (pintype "bidirectional"))
      (node (ref "U1") (pin "M8") (pinfunction "SW2_M8") (pintype "bidirectional"))
      (node (ref "U1") (pin "M9") (pinfunction "SW2_M9") (pintype "bidirectional"))
    )
    (net (code "36") (name "Net-(L2-Pad2)") (class "Default")
      (node (ref "L2") (pin "2") (pinfunction "2_2") (pintype "bidirectional"))
      (node (ref "U1") (pin "SW1@J1") (pinfunction "SW1_SW1@J1") (pintype "bidirectional"))
      (node (ref "U1") (pin "SW1@J2") (pinfunction "SW1_SW1@J2") (pintype "bidirectional"))
      (node (ref "U1") (pin "SW1@J3") (pinfunction "SW1_SW1@J3") (pintype "bidirectional"))
      (node (ref "U1") (pin "SW1@J4") (pinfunction "SW1_SW1@J4") (pintype "bidirectional"))
      (node (ref "U1") (pin "SW1@K1") (pinfunction "SW1_SW1@K1") (pintype "bidirectional"))
      (node (ref "U1") (pin "SW1@K2") (pinfunction "SW1_SW1@K2") (pintype "bidirectional"))
      (node (ref "U1") (pin "SW1@K3") (pinfunction "SW1_SW1@K3") (pintype "bidirectional"))
      (node (ref "U1") (pin "SW1@K4") (pinfunction "SW1_SW1@K4") (pintype "bidirectional"))
      (node (ref "U1") (pin "SW1@L1") (pinfunction "SW1_SW1@L1") (pintype "bidirectional"))
      (node (ref "U1") (pin "SW1@L2") (pinfunction "SW1_SW1@L2") (pintype "bidirectional"))
      (node (ref "U1") (pin "SW1@L3") (pinfunction "SW1_SW1@L3") (pintype "bidirectional"))
      (node (ref "U1") (pin "SW1@L4") (pinfunction "SW1_SW1@L4") (pintype "bidirectional"))
      (node (ref "U1") (pin "SW1@M1") (pinfunction "SW1_SW1@M1") (pintype "bidirectional"))
      (node (ref "U1") (pin "SW1@M2") (pinfunction "SW1_SW1@M2") (pintype "bidirectional"))
      (node (ref "U1") (pin "SW1@M3") (pinfunction "SW1_SW1@M3") (pintype "bidirectional"))
      (node (ref "U1") (pin "SW1@M4") (pinfunction "SW1_SW1@M4") (pintype "bidirectional"))
    )
    (net (code "37") (name "Net-(OK1-A1)") (class "Default")
      (node (ref "OK1") (pin "1") (pinfunction "A1_1") (pintype "bidirectional"))
      (node (ref "R5") (pin "2") (pinfunction "2_2") (pintype "passive"))
    )
    (net (code "38") (name "Net-(U1-PLLFLTR)") (class "Default")
      (node (ref "R1") (pin "2") (pinfunction "2_2") (pintype "passive"))
      (node (ref "R2") (pin "1") (pinfunction "1_1") (pintype "passive"))
      (node (ref "U1") (pin "B8") (pinfunction "PLLFLTR_B8") (pintype "bidirectional"))
    )
    (net (code "39") (name "Net-(U1-V_FB)") (class "Default")
      (node (ref "R4") (pin "2") (pinfunction "2_2") (pintype "passive"))
      (node (ref "U1") (pin "B6") (pinfunction "V_FB_B6") (pintype "bidirectional"))
    )
    (net (code "40") (name "OK1E1") (class "Default")
      (node (ref "OK2") (pin "15") (pinfunction "E1_15") (pintype "bidirectional"))
      (node (ref "R23") (pin "2") (pinfunction "2_2") (pintype "passive"))
      (node (ref "U3") (pin "3") (pinfunction "INPUT1_3") (pintype "bidirectional"))
    )
    (net (code "41") (name "OK1E2") (class "Default")
      (node (ref "OK2") (pin "13") (pinfunction "E2_13") (pintype "bidirectional"))
      (node (ref "R25") (pin "2") (pinfunction "2_2") (pintype "passive"))
      (node (ref "U3") (pin "5") (pinfunction "INPUT2_5") (pintype "bidirectional"))
    )
    (net (code "42") (name "OK1E3") (class "Default")
      (node (ref "OK2") (pin "11") (pinfunction "E3_11") (pintype "bidirectional"))
      (node (ref "R27") (pin "2") (pinfunction "2_2") (pintype "passive"))
      (node (ref "U3") (pin "7") (pinfunction "INPUT3_7") (pintype "bidirectional"))
    )
    (net (code "43") (name "OK1E4") (class "Default")
      (node (ref "OK2") (pin "9") (pinfunction "E4_9") (pintype "bidirectional"))
      (node (ref "R29") (pin "2") (pinfunction "2_2") (pintype "passive"))
      (node (ref "U3") (pin "9") (pinfunction "INPUT4_9") (pintype "bidirectional"))
    )
    (net (code "44") (name "OK2E1") (class "Default")
      (node (ref "OK3") (pin "15") (pinfunction "E1_15") (pintype "bidirectional"))
      (node (ref "R24") (pin "2") (pinfunction "2_2") (pintype "passive"))
      (node (ref "U4") (pin "3") (pinfunction "INPUT1_3") (pintype "bidirectional"))
    )
    (net (code "45") (name "OK2E2") (class "Default")
      (node (ref "OK3") (pin "13") (pinfunction "E2_13") (pintype "bidirectional"))
      (node (ref "R26") (pin "2") (pinfunction "2_2") (pintype "passive"))
      (node (ref "U4") (pin "5") (pinfunction "INPUT2_5") (pintype "bidirectional"))
    )
    (net (code "46") (name "OK2E3") (class "Default")
      (node (ref "OK3") (pin "11") (pinfunction "E3_11") (pintype "bidirectional"))
      (node (ref "R28") (pin "2") (pinfunction "2_2") (pintype "passive"))
      (node (ref "U4") (pin "7") (pinfunction "INPUT3_7") (pintype "bidirectional"))
    )
    (net (code "47") (name "OK2E4") (class "Default")
      (node (ref "OK3") (pin "9") (pinfunction "E4_9") (pintype "bidirectional"))
      (node (ref "R30") (pin "2") (pinfunction "2_2") (pintype "passive"))
      (node (ref "U4") (pin "9") (pinfunction "INPUT4_9") (pintype "bidirectional"))
    )
    (net (code "48") (name "P3") (class "Default")
      (node (ref "R5") (pin "1") (pinfunction "1_1") (pintype "passive"))
      (node (ref "SJ2") (pin "2") (pinfunction "2_2") (pintype "passive"))
      (node (ref "U2") (pin "17") (pinfunction "VCC3V_17") (pintype "bidirectional"))
      (node (ref "U2") (pin "47") (pinfunction "VCC3V_47") (pintype "bidirectional"))
    )
    (net (code "49") (name "P3_SW") (class "Default")
      (node (ref "J2") (pin "4") (pinfunction "4_4") (pintype "bidirectional"))
      (node (ref "J3") (pin "2") (pinfunction "2_2") (pintype "bidirectional"))
      (node (ref "SJ2") (pin "1") (pinfunction "1_1") (pintype "passive"))
    )
    (net (code "50") (name "P18_SW1") (class "Default")
      (node (ref "OK2") (pin "1") (pinfunction "A1_1") (pintype "bidirectional"))
      (node (ref "R7") (pin "1") (pinfunction "1_1") (pintype "passive"))
    )
    (net (code "51") (name "P18_SW2") (class "Default")
      (node (ref "OK2") (pin "5") (pinfunction "A3_5") (pintype "bidirectional"))
      (node (ref "R8") (pin "1") (pinfunction "1_1") (pintype "passive"))
    )
    (net (code "52") (name "P18_SW3") (class "Default")
      (node (ref "OK3") (pin "1") (pinfunction "A1_1") (pintype "bidirectional"))
      (node (ref "R9") (pin "1") (pinfunction "1_1") (pintype "passive"))
    )
    (net (code "53") (name "P18_SW4") (class "Default")
      (node (ref "OK3") (pin "5") (pinfunction "A3_5") (pintype "bidirectional"))
      (node (ref "R10") (pin "1") (pinfunction "1_1") (pintype "passive"))
    )
    (net (code "54") (name "P18_SW5") (class "Default")
      (node (ref "OK2") (pin "3") (pinfunction "A2_3") (pintype "bidirectional"))
      (node (ref "R11") (pin "1") (pinfunction "1_1") (pintype "passive"))
    )
    (net (code "55") (name "P18_SW6") (class "Default")
      (node (ref "OK2") (pin "7") (pinfunction "A4_7") (pintype "bidirectional"))
      (node (ref "R12") (pin "1") (pinfunction "1_1") (pintype "passive"))
    )
    (net (code "56") (name "P18_SW7") (class "Default")
      (node (ref "OK3") (pin "3") (pinfunction "A2_3") (pintype "bidirectional"))
      (node (ref "R13") (pin "1") (pinfunction "1_1") (pintype "passive"))
    )
    (net (code "57") (name "P18_SW8") (class "Default")
      (node (ref "OK3") (pin "7") (pinfunction "A4_7") (pintype "bidirectional"))
      (node (ref "R14") (pin "1") (pinfunction "1_1") (pintype "passive"))
    )
    (net (code "58") (name "PBATT_SW") (class "Default")
      (node (ref "SJ1") (pin "1") (pinfunction "1_1") (pintype "passive"))
    )
    (net (code "59") (name "PGND") (class "Default")
      (node (ref "C3") (pin "2") (pinfunction "2_2") (pintype "passive"))
      (node (ref "C4") (pin "2") (pinfunction "2_2") (pintype "passive"))
      (node (ref "C5") (pin "K1") (pinfunction "K_K1") (pintype "passive"))
      (node (ref "J3") (pin "1") (pinfunction "1_1") (pintype "bidirectional"))
      (node (ref "J4") (pin "1") (pinfunction "1_1") (pintype "bidirectional"))
      (node (ref "J4") (pin "4") (pinfunction "4_4") (pintype "bidirectional"))
      (node (ref "J5") (pin "1") (pinfunction "1_1") (pintype "bidirectional"))
      (node (ref "J5") (pin "4") (pinfunction "4_4") (pintype "bidirectional"))
      (node (ref "R23") (pin "1") (pinfunction "1_1") (pintype "passive"))
      (node (ref "R24") (pin "1") (pinfunction "1_1") (pintype "passive"))
      (node (ref "R25") (pin "1") (pinfunction "1_1") (pintype "passive"))
      (node (ref "R26") (pin "1") (pinfunction "1_1") (pintype "passive"))
      (node (ref "R27") (pin "1") (pinfunction "1_1") (pintype "passive"))
      (node (ref "R28") (pin "1") (pinfunction "1_1") (pintype "passive"))
      (node (ref "R29") (pin "1") (pinfunction "1_1") (pintype "passive"))
      (node (ref "R3") (pin "2") (pinfunction "2_2") (pintype "passive"))
      (node (ref "R30") (pin "1") (pinfunction "1_1") (pintype "passive"))
      (node (ref "R36") (pin "2") (pinfunction "2_2") (pintype "passive"))
      (node (ref "SJ4") (pin "2") (pinfunction "2_2") (pintype "passive"))
      (node (ref "U1") (pin "A1") (pinfunction "PGND_A1") (pintype "bidirectional"))
      (node (ref "U1") (pin "A11") (pinfunction "PGND_A11") (pintype "bidirectional"))
      (node (ref "U1") (pin "A12") (pinfunction "PGND_A12") (pintype "bidirectional"))
      (node (ref "U1") (pin "A2") (pinfunction "PGND_A2") (pintype "bidirectional"))
      (node (ref "U1") (pin "A3") (pinfunction "PGND_A3") (pintype "bidirectional"))
      (node (ref "U1") (pin "A5") (pinfunction "SENSE-_A5") (pintype "bidirectional"))
      (node (ref "U1") (pin "A7") (pinfunction "SGND_A7") (pintype "bidirectional"))
      (node (ref "U1") (pin "B1") (pinfunction "PGND_B1") (pintype "bidirectional"))
      (node (ref "U1") (pin "B10") (pinfunction "PGND_B10") (pintype "bidirectional"))
      (node (ref "U1") (pin "B11") (pinfunction "PGND_B11") (pintype "bidirectional"))
      (node (ref "U1") (pin "B12") (pinfunction "PGND_B12") (pintype "bidirectional"))
      (node (ref "U1") (pin "B2") (pinfunction "PGND_B2") (pintype "bidirectional"))
      (node (ref "U1") (pin "B3") (pinfunction "PGND_B3") (pintype "bidirectional"))
      (node (ref "U1") (pin "B4") (pinfunction "PGND_B4") (pintype "bidirectional"))
      (node (ref "U1") (pin "C1") (pinfunction "PGND_C1") (pintype "bidirectional"))
      (node (ref "U1") (pin "C10") (pinfunction "PGND_C10") (pintype "bidirectional"))
      (node (ref "U1") (pin "C11") (pinfunction "PGND_C11") (pintype "bidirectional"))
      (node (ref "U1") (pin "C12") (pinfunction "PGND_C12") (pintype "bidirectional"))
      (node (ref "U1") (pin "C2") (pinfunction "PGND_C2") (pintype "bidirectional"))
      (node (ref "U1") (pin "C3") (pinfunction "PGND_C3") (pintype "bidirectional"))
      (node (ref "U1") (pin "C4") (pinfunction "PGND_C4") (pintype "bidirectional"))
      (node (ref "U1") (pin "C5") (pinfunction "PGND_C5") (pintype "bidirectional"))
      (node (ref "U1") (pin "C6") (pinfunction "PGND_C6") (pintype "bidirectional"))
      (node (ref "U1") (pin "C7") (pinfunction "PGND_C7") (pintype "bidirectional"))
      (node (ref "U1") (pin "C8") (pinfunction "PGND_C8") (pintype "bidirectional"))
      (node (ref "U1") (pin "C9") (pinfunction "PGND_C9") (pintype "bidirectional"))
      (node (ref "U1") (pin "D1") (pinfunction "PGND_D1") (pintype "bidirectional"))
      (node (ref "U1") (pin "D10") (pinfunction "PGND_D10") (pintype "bidirectional"))
      (node (ref "U1") (pin "D11") (pinfunction "PGND_D11") (pintype "bidirectional"))
      (node (ref "U1") (pin "D12") (pinfunction "PGND_D12") (pintype "bidirectional"))
      (node (ref "U1") (pin "D2") (pinfunction "PGND_D2") (pintype "bidirectional"))
      (node (ref "U1") (pin "D3") (pinfunction "PGND_D3") (pintype "bidirectional"))
      (node (ref "U1") (pin "D4") (pinfunction "PGND_D4") (pintype "bidirectional"))
      (node (ref "U1") (pin "D5") (pinfunction "PGND_D5") (pintype "bidirectional"))
      (node (ref "U1") (pin "D6") (pinfunction "PGND_D6") (pintype "bidirectional"))
      (node (ref "U1") (pin "D7") (pinfunction "PGND_D7") (pintype "bidirectional"))
      (node (ref "U1") (pin "D8") (pinfunction "PGND_D8") (pintype "bidirectional"))
      (node (ref "U1") (pin "D9") (pinfunction "PGND_D9") (pintype "bidirectional"))
      (node (ref "U1") (pin "E10") (pinfunction "PGND_E10") (pintype "bidirectional"))
      (node (ref "U1") (pin "E11") (pinfunction "PGND_E11") (pintype "bidirectional"))
      (node (ref "U1") (pin "E12") (pinfunction "PGND_E12") (pintype "bidirectional"))
      (node (ref "U1") (pin "E3") (pinfunction "PGND_E3") (pintype "bidirectional"))
      (node (ref "U1") (pin "E4") (pinfunction "PGND_E4") (pintype "bidirectional"))
      (node (ref "U1") (pin "E5") (pinfunction "PGND_E5") (pintype "bidirectional"))
      (node (ref "U1") (pin "E6") (pinfunction "PGND_E6") (pintype "bidirectional"))
      (node (ref "U1") (pin "E7") (pinfunction "PGND_E7") (pintype "bidirectional"))
      (node (ref "U1") (pin "E8") (pinfunction "PGND_E8") (pintype "bidirectional"))
      (node (ref "U1") (pin "E9") (pinfunction "PGND_E9") (pintype "bidirectional"))
      (node (ref "U3") (pin "1") (pinfunction "GND_1") (pintype "bidirectional"))
      (node (ref "U3") (pin "10") (pinfunction "GND_10") (pintype "bidirectional"))
      (node (ref "U4") (pin "1") (pinfunction "GND_1") (pintype "bidirectional"))
      (node (ref "U4") (pin "10") (pinfunction "GND_10") (pintype "bidirectional"))
    )
    (net (code "60") (name "RSENSE") (class "Default")
      (node (ref "R3") (pin "1") (pinfunction "1_1") (pintype "passive"))
      (node (ref "U1") (pin "A4") (pinfunction "SENSE+_A4") (pintype "bidirectional"))
      (node (ref "U1") (pin "F10") (pinfunction "R_SENSE_F10") (pintype "bidirectional"))
      (node (ref "U1") (pin "F11") (pinfunction "R_SENSE_F11") (pintype "bidirectional"))
      (node (ref "U1") (pin "F12") (pinfunction "R_SENSE_F12") (pintype "bidirectional"))
      (node (ref "U1") (pin "G10") (pinfunction "R_SENSE_G10") (pintype "bidirectional"))
      (node (ref "U1") (pin "G11") (pinfunction "R_SENSE_G11") (pintype "bidirectional"))
      (node (ref "U1") (pin "G12") (pinfunction "R_SENSE_G12") (pintype "bidirectional"))
      (node (ref "U1") (pin "G5") (pinfunction "R_SENSE_G5") (pintype "bidirectional"))
      (node (ref "U1") (pin "G6") (pinfunction "R_SENSE_G6") (pintype "bidirectional"))
      (node (ref "U1") (pin "G7") (pinfunction "R_SENSE_G7") (pintype "bidirectional"))
      (node (ref "U1") (pin "G8") (pinfunction "R_SENSE_G8") (pintype "bidirectional"))
      (node (ref "U1") (pin "G9") (pinfunction "R_SENSE_G9") (pintype "bidirectional"))
      (node (ref "U1") (pin "H10") (pinfunction "R_SENSE_H10") (pintype "bidirectional"))
      (node (ref "U1") (pin "H11") (pinfunction "R_SENSE_H11") (pintype "bidirectional"))
      (node (ref "U1") (pin "H12") (pinfunction "R_SENSE_H12") (pintype "bidirectional"))
      (node (ref "U1") (pin "H5") (pinfunction "R_SENSE_H5") (pintype "bidirectional"))
      (node (ref "U1") (pin "H6") (pinfunction "R_SENSE_H6") (pintype "bidirectional"))
      (node (ref "U1") (pin "H7") (pinfunction "R_SENSE_H7") (pintype "bidirectional"))
      (node (ref "U1") (pin "H8") (pinfunction "R_SENSE_H8") (pintype "bidirectional"))
      (node (ref "U1") (pin "H9") (pinfunction "R_SENSE_H9") (pintype "bidirectional"))
      (node (ref "U1") (pin "J5") (pinfunction "R_SENSE_J5") (pintype "bidirectional"))
      (node (ref "U1") (pin "J6") (pinfunction "R_SENSE_J6") (pintype "bidirectional"))
      (node (ref "U1") (pin "J7") (pinfunction "R_SENSE_J7") (pintype "bidirectional"))
      (node (ref "U1") (pin "K5") (pinfunction "R_SENSE_K5") (pintype "bidirectional"))
      (node (ref "U1") (pin "K6") (pinfunction "R_SENSE_K6") (pintype "bidirectional"))
      (node (ref "U1") (pin "L5") (pinfunction "R_SENSE_L5") (pintype "bidirectional"))
      (node (ref "U1") (pin "L6") (pinfunction "R_SENSE_L6") (pintype "bidirectional"))
      (node (ref "U1") (pin "M5") (pinfunction "R_SENSE_M5") (pintype "bidirectional"))
      (node (ref "U1") (pin "M6") (pinfunction "R_SENSE_M6") (pintype "bidirectional"))
    )
    (net (code "61") (name "SGND") (class "Default")
      (node (ref "J4") (pin "12") (pinfunction "12_12") (pintype "bidirectional"))
      (node (ref "J4") (pin "9") (pinfunction "9_9") (pintype "bidirectional"))
      (node (ref "J5") (pin "12") (pinfunction "12_12") (pintype "bidirectional"))
      (node (ref "J5") (pin "9") (pinfunction "9_9") (pintype "bidirectional"))
      (node (ref "OK1") (pin "15") (pinfunction "E1_15") (pintype "bidirectional"))
      (node (ref "OK2") (pin "2") (pinfunction "K1_2") (pintype "bidirectional"))
      (node (ref "OK2") (pin "4") (pinfunction "K2_4") (pintype "bidirectional"))
      (node (ref "OK2") (pin "6") (pinfunction "K3_6") (pintype "bidirectional"))
      (node (ref "OK2") (pin "8") (pinfunction "K4_8") (pintype "bidirectional"))
      (node (ref "OK3") (pin "2") (pinfunction "K1_2") (pintype "bidirectional"))
      (node (ref "OK3") (pin "4") (pinfunction "K2_4") (pintype "bidirectional"))
      (node (ref "OK3") (pin "6") (pinfunction "K3_6") (pintype "bidirectional"))
      (node (ref "OK3") (pin "8") (pinfunction "K4_8") (pintype "bidirectional"))
      (node (ref "R2") (pin "2") (pinfunction "2_2") (pintype "passive"))
      (node (ref "SJ3") (pin "2") (pinfunction "2_2") (pintype "passive"))
    )
    (net (code "62") (name "SW_P18H1") (class "Default")
      (node (ref "R11") (pin "2") (pinfunction "2_2") (pintype "passive"))
      (node (ref "U2") (pin "35") (pinfunction "SDHC_DAT0_35") (pintype "bidirectional"))
    )
    (net (code "63") (name "SW_P18H2") (class "Default")
      (node (ref "R12") (pin "2") (pinfunction "2_2") (pintype "passive"))
      (node (ref "U2") (pin "34") (pinfunction "UART1_TX_34") (pintype "bidirectional"))
    )
    (net (code "64") (name "SW_P18H3") (class "Default")
      (node (ref "R13") (pin "2") (pinfunction "2_2") (pintype "passive"))
      (node (ref "U2") (pin "33") (pinfunction "SDHC_CMD_33") (pintype "bidirectional"))
    )
    (net (code "65") (name "SW_P18H4") (class "Default")
      (node (ref "R14") (pin "2") (pinfunction "2_2") (pintype "passive"))
      (node (ref "U2") (pin "32") (pinfunction "UART1_RX_32") (pintype "bidirectional"))
    )
    (net (code "66") (name "SW_P18L1") (class "Default")
      (node (ref "R7") (pin "2") (pinfunction "2_2") (pintype "passive"))
      (node (ref "U2") (pin "39") (pinfunction "SDHC_DAT2_39") (pintype "bidirectional"))
    )
    (net (code "67") (name "SW_P18L2") (class "Default")
      (node (ref "R8") (pin "2") (pinfunction "2_2") (pintype "passive"))
      (node (ref "U2") (pin "38") (pinfunction "UART1_CTS_38") (pintype "bidirectional"))
    )
    (net (code "68") (name "SW_P18L3") (class "Default")
      (node (ref "R9") (pin "2") (pinfunction "2_2") (pintype "passive"))
      (node (ref "U2") (pin "37") (pinfunction "SDHC_DAT1_37") (pintype "bidirectional"))
    )
    (net (code "69") (name "SW_P18L4") (class "Default")
      (node (ref "R10") (pin "2") (pinfunction "2_2") (pintype "passive"))
      (node (ref "U2") (pin "36") (pinfunction "UART1_RTS_36") (pintype "bidirectional"))
    )
    (net (code "70") (name "SW_RUNPMA") (class "Default")
      (node (ref "U1") (pin "A8") (pinfunction "RUN_A8") (pintype "bidirectional"))
      (node (ref "U2") (pin "23") (pinfunction "T2IN_23") (pintype "bidirectional"))
    )
    (net (code "71") (name "SW_TP1") (class "Default")
      (node (ref "J6") (pin "4") (pinfunction "4_4") (pintype "bidirectional"))
      (node (ref "OK1") (pin "2") (pinfunction "K1_2") (pintype "bidirectional"))
      (node (ref "U2") (pin "31") (pinfunction "SDHC_CLK_31") (pintype "bidirectional"))
    )
    (net (code "72") (name "TP1_OUT") (class "Default")
      (node (ref "J3") (pin "8") (pinfunction "8_8") (pintype "bidirectional"))
      (node (ref "J4") (pin "3") (pinfunction "3_3") (pintype "bidirectional"))
      (node (ref "J4") (pin "6") (pinfunction "6_6") (pintype "bidirectional"))
      (node (ref "J5") (pin "3") (pinfunction "3_3") (pintype "bidirectional"))
      (node (ref "J5") (pin "6") (pinfunction "6_6") (pintype "bidirectional"))
      (node (ref "OK1") (pin "16") (pinfunction "C1_16") (pintype "bidirectional"))
      (node (ref "R35") (pin "2") (pinfunction "2_2") (pintype "passive"))
      (node (ref "R36") (pin "1") (pinfunction "1_1") (pintype "passive"))
    )
    (net (code "73") (name "UART0_RX") (class "Default")
      (node (ref "J2") (pin "6") (pinfunction "6_6") (pintype "bidirectional"))
      (node (ref "J6") (pin "3") (pinfunction "3_3") (pintype "bidirectional"))
      (node (ref "U2") (pin "24") (pinfunction "UART0_RX_24") (pintype "bidirectional"))
    )
    (net (code "74") (name "UART0_TX") (class "Default")
      (node (ref "J2") (pin "3") (pinfunction "3_3") (pintype "bidirectional"))
      (node (ref "J6") (pin "2") (pinfunction "2_2") (pintype "bidirectional"))
      (node (ref "U2") (pin "26") (pinfunction "UART0_TX_26") (pintype "bidirectional"))
    )
    (net (code "75") (name "VBATT_IN") (class "Default")
      (node (ref "C1") (pin "A1") (pinfunction "A_A1") (pintype "passive"))
      (node (ref "J2") (pin "5") (pinfunction "5_5") (pintype "bidirectional"))
      (node (ref "J3") (pin "3") (pinfunction "3_3") (pintype "bidirectional"))
      (node (ref "L1") (pin "1") (pinfunction "1_1") (pintype "bidirectional"))
      (node (ref "SJ1") (pin "2") (pinfunction "2_2") (pintype "passive"))
    )
    (net (code "76") (name "VIN") (class "Default")
      (node (ref "C2") (pin "1") (pinfunction "1_1") (pintype "passive"))
      (node (ref "L1") (pin "2") (pinfunction "2_2") (pintype "bidirectional"))
      (node (ref "U1") (pin "J10") (pinfunction "V_IN_J10") (pintype "bidirectional"))
      (node (ref "U1") (pin "J11") (pinfunction "V_IN_J11") (pintype "bidirectional"))
      (node (ref "U1") (pin "J12") (pinfunction "V_IN_J12") (pintype "bidirectional"))
      (node (ref "U1") (pin "K10") (pinfunction "V_IN_K10") (pintype "bidirectional"))
      (node (ref "U1") (pin "K11") (pinfunction "V_IN_K11") (pintype "bidirectional"))
      (node (ref "U1") (pin "K12") (pinfunction "V_IN_K12") (pintype "bidirectional"))
      (node (ref "U1") (pin "L10") (pinfunction "V_IN_L10") (pintype "bidirectional"))
      (node (ref "U1") (pin "L11") (pinfunction "V_IN_L11") (pintype "bidirectional"))
      (node (ref "U1") (pin "L12") (pinfunction "V_IN_L12") (pintype "bidirectional"))
      (node (ref "U1") (pin "M10") (pinfunction "V_IN_M10") (pintype "bidirectional"))
      (node (ref "U1") (pin "M11") (pinfunction "V_IN_M11") (pintype "bidirectional"))
      (node (ref "U1") (pin "M12") (pinfunction "V_IN_M12") (pintype "bidirectional"))
    )
    (net (code "77") (name "VOUT") (class "Default")
      (node (ref "C3") (pin "1") (pinfunction "1_1") (pintype "passive"))
      (node (ref "C4") (pin "1") (pinfunction "1_1") (pintype "passive"))
      (node (ref "L3") (pin "1") (pinfunction "1_1") (pintype "bidirectional"))
      (node (ref "U1") (pin "E1") (pinfunction "V_OUT_E1") (pintype "bidirectional"))
      (node (ref "U1") (pin "E2") (pinfunction "V_OUT_E2") (pintype "bidirectional"))
      (node (ref "U1") (pin "F1") (pinfunction "V_OUT_F1") (pintype "bidirectional"))
      (node (ref "U1") (pin "F2") (pinfunction "V_OUT_F2") (pintype "bidirectional"))
      (node (ref "U1") (pin "F3") (pinfunction "V_OUT_F3") (pintype "bidirectional"))
      (node (ref "U1") (pin "F4") (pinfunction "V_OUT_F4") (pintype "bidirectional"))
      (node (ref "U1") (pin "G1") (pinfunction "V_OUT_G1") (pintype "bidirectional"))
      (node (ref "U1") (pin "G2") (pinfunction "V_OUT_G2") (pintype "bidirectional"))
      (node (ref "U1") (pin "G3") (pinfunction "V_OUT_G3") (pintype "bidirectional"))
      (node (ref "U1") (pin "G4") (pinfunction "V_OUT_G4") (pintype "bidirectional"))
      (node (ref "U1") (pin "H2") (pinfunction "V_OUT_H2") (pintype "bidirectional"))
      (node (ref "U1") (pin "H3") (pinfunction "V_OUT_H3") (pintype "bidirectional"))
      (node (ref "U1") (pin "H4") (pinfunction "V_OUT_H4") (pintype "bidirectional"))
      (node (ref "U1") (pin "VOUT") (pinfunction "V_OUT_VOUT") (pintype "bidirectional"))
    )
    (net (code "78") (name "VOUTA") (class "Default")
      (node (ref "C5") (pin "A1") (pinfunction "A_A1") (pintype "passive"))
      (node (ref "J3") (pin "6") (pinfunction "6_6") (pintype "bidirectional"))
      (node (ref "L3") (pin "2") (pinfunction "2_2") (pintype "bidirectional"))
      (node (ref "Q1") (pin "D") (pinfunction "D_D") (pintype "bidirectional"))
      (node (ref "Q3") (pin "D") (pinfunction "D_D") (pintype "bidirectional"))
      (node (ref "Q5") (pin "D") (pinfunction "D_D") (pintype "bidirectional"))
      (node (ref "Q7") (pin "D") (pinfunction "D_D") (pintype "bidirectional"))
      (node (ref "R15") (pin "1") (pinfunction "1_1") (pintype "passive"))
      (node (ref "R16") (pin "1") (pinfunction "1_1") (pintype "passive"))
      (node (ref "R17") (pin "1") (pinfunction "1_1") (pintype "passive"))
      (node (ref "R18") (pin "1") (pinfunction "1_1") (pintype "passive"))
      (node (ref "R19") (pin "1") (pinfunction "1_1") (pintype "passive"))
      (node (ref "R20") (pin "1") (pinfunction "1_1") (pintype "passive"))
      (node (ref "R21") (pin "1") (pinfunction "1_1") (pintype "passive"))
      (node (ref "R22") (pin "1") (pinfunction "1_1") (pintype "passive"))
      (node (ref "R31") (pin "2") (pinfunction "2_2") (pintype "passive"))
      (node (ref "R32") (pin "2") (pinfunction "2_2") (pintype "passive"))
      (node (ref "R33") (pin "2") (pinfunction "2_2") (pintype "passive"))
      (node (ref "R34") (pin "2") (pinfunction "2_2") (pintype "passive"))
      (node (ref "R35") (pin "1") (pinfunction "1_1") (pintype "passive"))
      (node (ref "U3") (pin "11") (pinfunction "V+_11") (pintype "bidirectional"))
      (node (ref "U3") (pin "13") (pinfunction "SENSE4_13") (pintype "bidirectional"))
      (node (ref "U3") (pin "15") (pinfunction "SENSE3_15") (pintype "bidirectional"))
      (node (ref "U3") (pin "17") (pinfunction "SENSE2_17") (pintype "bidirectional"))
      (node (ref "U3") (pin "19") (pinfunction "SENSE1_19") (pintype "bidirectional"))
      (node (ref "U3") (pin "20") (pinfunction "V+_20") (pintype "bidirectional"))
      (node (ref "U4") (pin "11") (pinfunction "V+_11") (pintype "bidirectional"))
      (node (ref "U4") (pin "13") (pinfunction "SENSE4_13") (pintype "bidirectional"))
      (node (ref "U4") (pin "15") (pinfunction "SENSE3_15") (pintype "bidirectional"))
      (node (ref "U4") (pin "17") (pinfunction "SENSE2_17") (pintype "bidirectional"))
      (node (ref "U4") (pin "19") (pinfunction "SENSE1_19") (pintype "bidirectional"))
      (node (ref "U4") (pin "20") (pinfunction "V+_20") (pintype "bidirectional"))
    )
    (net (code "79") (name "unconnected-(J1-+5V_SW-Pad33)") (class "Default")
      (node (ref "J1") (pin "33") (pinfunction "+5V_SW_33") (pintype "bidirectional"))
    )
    (net (code "80") (name "unconnected-(J1-+5V_SYS-Pad77)") (class "Default")
      (node (ref "J1") (pin "77") (pinfunction "+5V_SYS_77") (pintype "bidirectional"))
    )
    (net (code "81") (name "unconnected-(J1-+5V_SYS-Pad78)") (class "Default")
      (node (ref "J1") (pin "78") (pinfunction "+5V_SYS_78") (pintype "bidirectional"))
    )
    (net (code "82") (name "unconnected-(J1-+5V_USB-Pad32)") (class "Default")
      (node (ref "J1") (pin "32") (pinfunction "+5V_USB_32") (pintype "bidirectional"))
    )
    (net (code "83") (name "unconnected-(J1--CTS_MHX-Pad35)") (class "Default")
      (node (ref "J1") (pin "35") (pinfunction "-CTS_MHX_35") (pintype "bidirectional"))
    )
    (net (code "84") (name "unconnected-(J1--DSR_MHX-Pad37)") (class "Default")
      (node (ref "J1") (pin "37") (pinfunction "-DSR_MHX_37") (pintype "bidirectional"))
    )
    (net (code "85") (name "unconnected-(J1--DTR_MHX-Pad38)") (class "Default")
      (node (ref "J1") (pin "38") (pinfunction "-DTR_MHX_38") (pintype "bidirectional"))
    )
    (net (code "86") (name "unconnected-(J1--FAULT-Pad25)") (class "Default")
      (node (ref "J1") (pin "25") (pinfunction "-FAULT_25") (pintype "bidirectional"))
    )
    (net (code "87") (name "unconnected-(J1--RESET-Pad29)") (class "Default")
      (node (ref "J1") (pin "29") (pinfunction "-RESET_29") (pintype "bidirectional"))
    )
    (net (code "88") (name "unconnected-(J1--RST_MHX-Pad34)") (class "Default")
      (node (ref "J1") (pin "34") (pinfunction "-RST_MHX_34") (pintype "bidirectional"))
    )
    (net (code "89") (name "unconnected-(J1--RTS_MHX-Pad36)") (class "Default")
      (node (ref "J1") (pin "36") (pinfunction "-RTS_MHX_36") (pintype "bidirectional"))
    )
    (net (code "90") (name "unconnected-(J1-OFF_VCC-Pad31)") (class "Default")
      (node (ref "J1") (pin "31") (pinfunction "OFF_VCC_31") (pintype "bidirectional"))
    )
    (net (code "91") (name "unconnected-(J1-P1.0-Pad68)") (class "Default")
      (node (ref "J1") (pin "68") (pinfunction "P1.0_68") (pintype "bidirectional"))
    )
    (net (code "92") (name "unconnected-(J1-P1.1-Pad67)") (class "Default")
      (node (ref "J1") (pin "67") (pinfunction "P1.1_67") (pintype "bidirectional"))
    )
    (net (code "93") (name "unconnected-(J1-P1.2-Pad66)") (class "Default")
      (node (ref "J1") (pin "66") (pinfunction "P1.2_66") (pintype "bidirectional"))
    )
    (net (code "94") (name "unconnected-(J1-P1.3-Pad65)") (class "Default")
      (node (ref "J1") (pin "65") (pinfunction "P1.3_65") (pintype "bidirectional"))
    )
    (net (code "95") (name "unconnected-(J1-P1.4-Pad64)") (class "Default")
      (node (ref "J1") (pin "64") (pinfunction "P1.4_64") (pintype "bidirectional"))
    )
    (net (code "96") (name "unconnected-(J1-P1.5-Pad63)") (class "Default")
      (node (ref "J1") (pin "63") (pinfunction "P1.5_63") (pintype "bidirectional"))
    )
    (net (code "97") (name "unconnected-(J1-P1.6-Pad62)") (class "Default")
      (node (ref "J1") (pin "62") (pinfunction "P1.6_62") (pintype "bidirectional"))
    )
    (net (code "98") (name "unconnected-(J1-P1.7-Pad61)") (class "Default")
      (node (ref "J1") (pin "61") (pinfunction "P1.7_61") (pintype "bidirectional"))
    )
    (net (code "99") (name "unconnected-(J1-P2.0-Pad76)") (class "Default")
      (node (ref "J1") (pin "76") (pinfunction "P2.0_76") (pintype "bidirectional"))
    )
    (net (code "100") (name "unconnected-(J1-P2.1-Pad75)") (class "Default")
      (node (ref "J1") (pin "75") (pinfunction "P2.1_75") (pintype "bidirectional"))
    )
    (net (code "101") (name "unconnected-(J1-P2.2-Pad74)") (class "Default")
      (node (ref "J1") (pin "74") (pinfunction "P2.2_74") (pintype "bidirectional"))
    )
    (net (code "102") (name "unconnected-(J1-P2.3-Pad73)") (class "Default")
      (node (ref "J1") (pin "73") (pinfunction "P2.3_73") (pintype "bidirectional"))
    )
    (net (code "103") (name "unconnected-(J1-P2.4-Pad72)") (class "Default")
      (node (ref "J1") (pin "72") (pinfunction "P2.4_72") (pintype "bidirectional"))
    )
    (net (code "104") (name "unconnected-(J1-P2.5-Pad71)") (class "Default")
      (node (ref "J1") (pin "71") (pinfunction "P2.5_71") (pintype "bidirectional"))
    )
    (net (code "105") (name "unconnected-(J1-P2.6-Pad70)") (class "Default")
      (node (ref "J1") (pin "70") (pinfunction "P2.6_70") (pintype "bidirectional"))
    )
    (net (code "106") (name "unconnected-(J1-P2.7-Pad69)") (class "Default")
      (node (ref "J1") (pin "69") (pinfunction "P2.7_69") (pintype "bidirectional"))
    )
    (net (code "107") (name "unconnected-(J1-P3.0-Pad24)") (class "Default")
      (node (ref "J1") (pin "24") (pinfunction "P3.0_24") (pintype "bidirectional"))
    )
    (net (code "108") (name "unconnected-(J1-P3.1-Pad23)") (class "Default")
      (node (ref "J1") (pin "23") (pinfunction "P3.1_23") (pintype "bidirectional"))
    )
    (net (code "109") (name "unconnected-(J1-P3.2-Pad22)") (class "Default")
      (node (ref "J1") (pin "22") (pinfunction "P3.2_22") (pintype "bidirectional"))
    )
    (net (code "110") (name "unconnected-(J1-P3.3-Pad21)") (class "Default")
      (node (ref "J1") (pin "21") (pinfunction "P3.3_21") (pintype "bidirectional"))
    )
    (net (code "111") (name "unconnected-(J1-P3.4-Pad20)") (class "Default")
      (node (ref "J1") (pin "20") (pinfunction "P3.4_20") (pintype "bidirectional"))
    )
    (net (code "112") (name "unconnected-(J1-P3.5-Pad19)") (class "Default")
      (node (ref "J1") (pin "19") (pinfunction "P3.5_19") (pintype "bidirectional"))
    )
    (net (code "113") (name "unconnected-(J1-P3.6-Pad18)") (class "Default")
      (node (ref "J1") (pin "18") (pinfunction "P3.6_18") (pintype "bidirectional"))
    )
    (net (code "114") (name "unconnected-(J1-P3.7-Pad17)") (class "Default")
      (node (ref "J1") (pin "17") (pinfunction "P3.7_17") (pintype "bidirectional"))
    )
    (net (code "115") (name "unconnected-(J1-P4.0-Pad16)") (class "Default")
      (node (ref "J1") (pin "16") (pinfunction "P4.0_16") (pintype "bidirectional"))
    )
    (net (code "116") (name "unconnected-(J1-P4.1-Pad15)") (class "Default")
      (node (ref "J1") (pin "15") (pinfunction "P4.1_15") (pintype "bidirectional"))
    )
    (net (code "117") (name "unconnected-(J1-P4.2-Pad14)") (class "Default")
      (node (ref "J1") (pin "14") (pinfunction "P4.2_14") (pintype "bidirectional"))
    )
    (net (code "118") (name "unconnected-(J1-P4.3-Pad13)") (class "Default")
      (node (ref "J1") (pin "13") (pinfunction "P4.3_13") (pintype "bidirectional"))
    )
    (net (code "119") (name "unconnected-(J1-P4.4-Pad12)") (class "Default")
      (node (ref "J1") (pin "12") (pinfunction "P4.4_12") (pintype "bidirectional"))
    )
    (net (code "120") (name "unconnected-(J1-P4.5-Pad11)") (class "Default")
      (node (ref "J1") (pin "11") (pinfunction "P4.5_11") (pintype "bidirectional"))
    )
    (net (code "121") (name "unconnected-(J1-P4.6-Pad10)") (class "Default")
      (node (ref "J1") (pin "10") (pinfunction "P4.6_10") (pintype "bidirectional"))
    )
    (net (code "122") (name "unconnected-(J1-P4.7-Pad9)") (class "Default")
      (node (ref "J1") (pin "9") (pinfunction "P4.7_9") (pintype "bidirectional"))
    )
    (net (code "123") (name "unconnected-(J1-P5.0-Pad8)") (class "Default")
      (node (ref "J1") (pin "8") (pinfunction "P5.0_8") (pintype "bidirectional"))
    )
    (net (code "124") (name "unconnected-(J1-P5.1-Pad7)") (class "Default")
      (node (ref "J1") (pin "7") (pinfunction "P5.1_7") (pintype "bidirectional"))
    )
    (net (code "125") (name "unconnected-(J1-P5.2-Pad6)") (class "Default")
      (node (ref "J1") (pin "6") (pinfunction "P5.2_6") (pintype "bidirectional"))
    )
    (net (code "126") (name "unconnected-(J1-P5.3-Pad5)") (class "Default")
      (node (ref "J1") (pin "5") (pinfunction "P5.3_5") (pintype "bidirectional"))
    )
    (net (code "127") (name "unconnected-(J1-P5.4-Pad4)") (class "Default")
      (node (ref "J1") (pin "4") (pinfunction "P5.4_4") (pintype "bidirectional"))
    )
    (net (code "128") (name "unconnected-(J1-P5.5-Pad3)") (class "Default")
      (node (ref "J1") (pin "3") (pinfunction "P5.5_3") (pintype "bidirectional"))
    )
    (net (code "129") (name "unconnected-(J1-P5.6-Pad2)") (class "Default")
      (node (ref "J1") (pin "2") (pinfunction "P5.6_2") (pintype "bidirectional"))
    )
    (net (code "130") (name "unconnected-(J1-P5.7-Pad1)") (class "Default")
      (node (ref "J1") (pin "1") (pinfunction "P5.7_1") (pintype "bidirectional"))
    )
    (net (code "131") (name "unconnected-(J1-P6.0-Pad60)") (class "Default")
      (node (ref "J1") (pin "60") (pinfunction "P6.0_60") (pintype "bidirectional"))
    )
    (net (code "132") (name "unconnected-(J1-P6.1-Pad59)") (class "Default")
      (node (ref "J1") (pin "59") (pinfunction "P6.1_59") (pintype "bidirectional"))
    )
    (net (code "133") (name "unconnected-(J1-P6.2-Pad58)") (class "Default")
      (node (ref "J1") (pin "58") (pinfunction "P6.2_58") (pintype "bidirectional"))
    )
    (net (code "134") (name "unconnected-(J1-P6.3-Pad57)") (class "Default")
      (node (ref "J1") (pin "57") (pinfunction "P6.3_57") (pintype "bidirectional"))
    )
    (net (code "135") (name "unconnected-(J1-P6.4-Pad56)") (class "Default")
      (node (ref "J1") (pin "56") (pinfunction "P6.4_56") (pintype "bidirectional"))
    )
    (net (code "136") (name "unconnected-(J1-P6.5-Pad55)") (class "Default")
      (node (ref "J1") (pin "55") (pinfunction "P6.5_55") (pintype "bidirectional"))
    )
    (net (code "137") (name "unconnected-(J1-P6.6-Pad54)") (class "Default")
      (node (ref "J1") (pin "54") (pinfunction "P6.6_54") (pintype "bidirectional"))
    )
    (net (code "138") (name "unconnected-(J1-P6.7-Pad53)") (class "Default")
      (node (ref "J1") (pin "53") (pinfunction "P6.7_53") (pintype "bidirectional"))
    )
    (net (code "139") (name "unconnected-(J1-RSVD0-Pad44)") (class "Default")
      (node (ref "J1") (pin "44") (pinfunction "RSVD0_44") (pintype "bidirectional"))
    )
    (net (code "140") (name "unconnected-(J1-RSVD1-Pad45)") (class "Default")
      (node (ref "J1") (pin "45") (pinfunction "RSVD1_45") (pintype "bidirectional"))
    )
    (net (code "141") (name "unconnected-(J1-RSVD2-Pad46)") (class "Default")
      (node (ref "J1") (pin "46") (pinfunction "RSVD2_46") (pintype "bidirectional"))
    )
    (net (code "142") (name "unconnected-(J1-RXD_MHX-Pad40)") (class "Default")
      (node (ref "J1") (pin "40") (pinfunction "RXD_MHX_40") (pintype "bidirectional"))
    )
    (net (code "143") (name "unconnected-(J1-SENSE-Pad27)") (class "Default")
      (node (ref "J1") (pin "27") (pinfunction "SENSE_27") (pintype "bidirectional"))
    )
    (net (code "144") (name "unconnected-(J1-SW0-Pad85)") (class "Default")
      (node (ref "J1") (pin "85") (pinfunction "SW0_85") (pintype "bidirectional"))
    )
    (net (code "145") (name "unconnected-(J1-SW0-Pad86)") (class "Default")
      (node (ref "J1") (pin "86") (pinfunction "SW0_86") (pintype "bidirectional"))
    )
    (net (code "146") (name "unconnected-(J1-SW1-Pad87)") (class "Default")
      (node (ref "J1") (pin "87") (pinfunction "SW1_87") (pintype "bidirectional"))
    )
    (net (code "147") (name "unconnected-(J1-SW1-Pad88)") (class "Default")
      (node (ref "J1") (pin "88") (pinfunction "SW1_88") (pintype "bidirectional"))
    )
    (net (code "148") (name "unconnected-(J1-SW2-Pad89)") (class "Default")
      (node (ref "J1") (pin "89") (pinfunction "SW2_89") (pintype "bidirectional"))
    )
    (net (code "149") (name "unconnected-(J1-SW2-Pad90)") (class "Default")
      (node (ref "J1") (pin "90") (pinfunction "SW2_90") (pintype "bidirectional"))
    )
    (net (code "150") (name "unconnected-(J1-SW3-Pad91)") (class "Default")
      (node (ref "J1") (pin "91") (pinfunction "SW3_91") (pintype "bidirectional"))
    )
    (net (code "151") (name "unconnected-(J1-SW3-Pad92)") (class "Default")
      (node (ref "J1") (pin "92") (pinfunction "SW3_92") (pintype "bidirectional"))
    )
    (net (code "152") (name "unconnected-(J1-SW4-Pad93)") (class "Default")
      (node (ref "J1") (pin "93") (pinfunction "SW4_93") (pintype "bidirectional"))
    )
    (net (code "153") (name "unconnected-(J1-SW4-Pad94)") (class "Default")
      (node (ref "J1") (pin "94") (pinfunction "SW4_94") (pintype "bidirectional"))
    )
    (net (code "154") (name "unconnected-(J1-SW5-Pad95)") (class "Default")
      (node (ref "J1") (pin "95") (pinfunction "SW5_95") (pintype "bidirectional"))
    )
    (net (code "155") (name "unconnected-(J1-SW5-Pad96)") (class "Default")
      (node (ref "J1") (pin "96") (pinfunction "SW5_96") (pintype "bidirectional"))
    )
    (net (code "156") (name "unconnected-(J1-TXD_MHX-Pad39)") (class "Default")
      (node (ref "J1") (pin "39") (pinfunction "TXD_MHX_39") (pintype "bidirectional"))
    )
    (net (code "157") (name "unconnected-(J1-USER0-Pad47)") (class "Default")
      (node (ref "J1") (pin "47") (pinfunction "USER0_47") (pintype "bidirectional"))
    )
    (net (code "158") (name "unconnected-(J1-USER1-Pad48)") (class "Default")
      (node (ref "J1") (pin "48") (pinfunction "USER1_48") (pintype "bidirectional"))
    )
    (net (code "159") (name "unconnected-(J1-USER2-Pad49)") (class "Default")
      (node (ref "J1") (pin "49") (pinfunction "USER2_49") (pintype "bidirectional"))
    )
    (net (code "160") (name "unconnected-(J1-USER3-Pad50)") (class "Default")
      (node (ref "J1") (pin "50") (pinfunction "USER3_50") (pintype "bidirectional"))
    )
    (net (code "161") (name "unconnected-(J1-USER4-Pad51)") (class "Default")
      (node (ref "J1") (pin "51") (pinfunction "USER4_51") (pintype "bidirectional"))
    )
    (net (code "162") (name "unconnected-(J1-USER5-Pad52)") (class "Default")
      (node (ref "J1") (pin "52") (pinfunction "USER5_52") (pintype "bidirectional"))
    )
    (net (code "163") (name "unconnected-(J1-USER6-Pad99)") (class "Default")
      (node (ref "J1") (pin "99") (pinfunction "USER6_99") (pintype "bidirectional"))
    )
    (net (code "164") (name "unconnected-(J1-USER7-Pad100)") (class "Default")
      (node (ref "J1") (pin "100") (pinfunction "USER7_100") (pintype "bidirectional"))
    )
    (net (code "165") (name "unconnected-(J1-USER8-Pad101)") (class "Default")
      (node (ref "J1") (pin "101") (pinfunction "USER8_101") (pintype "bidirectional"))
    )
    (net (code "166") (name "unconnected-(J1-USER9-Pad102)") (class "Default")
      (node (ref "J1") (pin "102") (pinfunction "USER9_102") (pintype "bidirectional"))
    )
    (net (code "167") (name "unconnected-(J1-USER10-Pad103)") (class "Default")
      (node (ref "J1") (pin "103") (pinfunction "USER10_103") (pintype "bidirectional"))
    )
    (net (code "168") (name "unconnected-(J1-USER11-Pad104)") (class "Default")
      (node (ref "J1") (pin "104") (pinfunction "USER11_104") (pintype "bidirectional"))
    )
    (net (code "169") (name "unconnected-(J1-VBACKUP-Pad42)") (class "Default")
      (node (ref "J1") (pin "42") (pinfunction "VBACKUP_42") (pintype "bidirectional"))
    )
    (net (code "170") (name "unconnected-(J1-VBATT-Pad97)") (class "Default")
      (node (ref "J1") (pin "97") (pinfunction "VBATT_97") (pintype "bidirectional"))
    )
    (net (code "171") (name "unconnected-(J1-VBATT-Pad98)") (class "Default")
      (node (ref "J1") (pin "98") (pinfunction "VBATT_98") (pintype "bidirectional"))
    )
    (net (code "172") (name "unconnected-(J1-VCC_SYS-Pad79)") (class "Default")
      (node (ref "J1") (pin "79") (pinfunction "VCC_SYS_79") (pintype "bidirectional"))
    )
    (net (code "173") (name "unconnected-(J1-VCC_SYS-Pad80)") (class "Default")
      (node (ref "J1") (pin "80") (pinfunction "VCC_SYS_80") (pintype "bidirectional"))
    )
    (net (code "174") (name "unconnected-(J1-VEREF+-Pad28)") (class "Default")
      (node (ref "J1") (pin "28") (pinfunction "VEREF+_28") (pintype "bidirectional"))
    )
    (net (code "175") (name "unconnected-(J1-VREF+-Pad26)") (class "Default")
      (node (ref "J1") (pin "26") (pinfunction "VREF+_26") (pintype "bidirectional"))
    )
    (net (code "176") (name "unconnected-(J1-VREF--Pad30)") (class "Default")
      (node (ref "J1") (pin "30") (pinfunction "VREF-_30") (pintype "bidirectional"))
    )
    (net (code "177") (name "unconnected-(J3-Pad7)") (class "Default")
      (node (ref "J3") (pin "7") (pinfunction "7_7") (pintype "bidirectional"))
    )
    (net (code "178") (name "unconnected-(J4-Pad2)") (class "Default")
      (node (ref "J4") (pin "2") (pinfunction "2_2") (pintype "bidirectional"))
    )
    (net (code "179") (name "unconnected-(J4-Pad5)") (class "Default")
      (node (ref "J4") (pin "5") (pinfunction "5_5") (pintype "bidirectional"))
    )
    (net (code "180") (name "unconnected-(J5-Pad2)") (class "Default")
      (node (ref "J5") (pin "2") (pinfunction "2_2") (pintype "bidirectional"))
    )
    (net (code "181") (name "unconnected-(J5-Pad5)") (class "Default")
      (node (ref "J5") (pin "5") (pinfunction "5_5") (pintype "bidirectional"))
    )
    (net (code "182") (name "unconnected-(J6-Pad5)") (class "Default")
      (node (ref "J6") (pin "5") (pinfunction "5_5") (pintype "bidirectional"))
    )
    (net (code "183") (name "unconnected-(J6-Pad6)") (class "Default")
      (node (ref "J6") (pin "6") (pinfunction "6_6") (pintype "bidirectional"))
    )
    (net (code "184") (name "unconnected-(J6-Pad7)") (class "Default")
      (node (ref "J6") (pin "7") (pinfunction "7_7") (pintype "bidirectional"))
    )
    (net (code "185") (name "unconnected-(J6-Pad8)") (class "Default")
      (node (ref "J6") (pin "8") (pinfunction "8_8") (pintype "bidirectional"))
    )
    (net (code "186") (name "unconnected-(J6-Pad9)") (class "Default")
      (node (ref "J6") (pin "9") (pinfunction "9_9") (pintype "bidirectional"))
    )
    (net (code "187") (name "unconnected-(J6-Pad10)") (class "Default")
      (node (ref "J6") (pin "10") (pinfunction "10_10") (pintype "bidirectional"))
    )
    (net (code "188") (name "unconnected-(OK1-A2-Pad3)") (class "Default")
      (node (ref "OK1") (pin "3") (pinfunction "A2_3") (pintype "bidirectional"))
    )
    (net (code "189") (name "unconnected-(OK1-A3-Pad5)") (class "Default")
      (node (ref "OK1") (pin "5") (pinfunction "A3_5") (pintype "bidirectional"))
    )
    (net (code "190") (name "unconnected-(OK1-A4-Pad7)") (class "Default")
      (node (ref "OK1") (pin "7") (pinfunction "A4_7") (pintype "bidirectional"))
    )
    (net (code "191") (name "unconnected-(OK1-C2-Pad14)") (class "Default")
      (node (ref "OK1") (pin "14") (pinfunction "C2_14") (pintype "bidirectional"))
    )
    (net (code "192") (name "unconnected-(OK1-C3-Pad12)") (class "Default")
      (node (ref "OK1") (pin "12") (pinfunction "C3_12") (pintype "bidirectional"))
    )
    (net (code "193") (name "unconnected-(OK1-C4-Pad10)") (class "Default")
      (node (ref "OK1") (pin "10") (pinfunction "C4_10") (pintype "bidirectional"))
    )
    (net (code "194") (name "unconnected-(OK1-E2-Pad13)") (class "Default")
      (node (ref "OK1") (pin "13") (pinfunction "E2_13") (pintype "bidirectional"))
    )
    (net (code "195") (name "unconnected-(OK1-E3-Pad11)") (class "Default")
      (node (ref "OK1") (pin "11") (pinfunction "E3_11") (pintype "bidirectional"))
    )
    (net (code "196") (name "unconnected-(OK1-E4-Pad9)") (class "Default")
      (node (ref "OK1") (pin "9") (pinfunction "E4_9") (pintype "bidirectional"))
    )
    (net (code "197") (name "unconnected-(OK1-K2-Pad4)") (class "Default")
      (node (ref "OK1") (pin "4") (pinfunction "K2_4") (pintype "bidirectional"))
    )
    (net (code "198") (name "unconnected-(OK1-K3-Pad6)") (class "Default")
      (node (ref "OK1") (pin "6") (pinfunction "K3_6") (pintype "bidirectional"))
    )
    (net (code "199") (name "unconnected-(OK1-K4-Pad8)") (class "Default")
      (node (ref "OK1") (pin "8") (pinfunction "K4_8") (pintype "bidirectional"))
    )
    (net (code "200") (name "unconnected-(U1-COMP-PadB7)") (class "Default")
      (node (ref "U1") (pin "B7") (pinfunction "COMP_B7") (pintype "bidirectional"))
    )
    (net (code "201") (name "unconnected-(U1-EXTV_CC-PadF6)") (class "Default")
      (node (ref "U1") (pin "F6") (pinfunction "EXTV_CC_F6") (pintype "bidirectional"))
    )
    (net (code "202") (name "unconnected-(U1-PGOOD-PadB5)") (class "Default")
      (node (ref "U1") (pin "B5") (pinfunction "PGOOD_B5") (pintype "bidirectional"))
    )
    (net (code "203") (name "unconnected-(U1-PLLIN-PadB9)") (class "Default")
      (node (ref "U1") (pin "B9") (pinfunction "PLLIN_B9") (pintype "bidirectional"))
    )
    (net (code "204") (name "unconnected-(U1-SS-PadA6)") (class "Default")
      (node (ref "U1") (pin "A6") (pinfunction "SS_A6") (pintype "bidirectional"))
    )
    (net (code "205") (name "unconnected-(U1-STBYMD-PadA10)") (class "Default")
      (node (ref "U1") (pin "A10") (pinfunction "STBYMD_A10") (pintype "bidirectional"))
    )
    (net (code "206") (name "unconnected-(U2-ADC_IN0-Pad2)") (class "Default")
      (node (ref "U2") (pin "2") (pinfunction "ADC_IN0_2") (pintype "bidirectional"))
    )
    (net (code "207") (name "unconnected-(U2-ADC_IN1-Pad1)") (class "Default")
      (node (ref "U2") (pin "1") (pinfunction "ADC_IN1_1") (pintype "bidirectional"))
    )
    (net (code "208") (name "unconnected-(U2-ADC_IN2-Pad4)") (class "Default")
      (node (ref "U2") (pin "4") (pinfunction "ADC_IN2_4") (pintype "bidirectional"))
    )
    (net (code "209") (name "unconnected-(U2-ADC_IN3-Pad3)") (class "Default")
      (node (ref "U2") (pin "3") (pinfunction "ADC_IN3_3") (pintype "bidirectional"))
    )
    (net (code "210") (name "unconnected-(U2-ADC_IN4-Pad6)") (class "Default")
      (node (ref "U2") (pin "6") (pinfunction "ADC_IN4_6") (pintype "bidirectional"))
    )
    (net (code "211") (name "unconnected-(U2-ADC_IN7-Pad5)") (class "Default")
      (node (ref "U2") (pin "5") (pinfunction "ADC_IN7_5") (pintype "bidirectional"))
    )
    (net (code "212") (name "unconnected-(U2-AGND-Pad8)") (class "Default")
      (node (ref "U2") (pin "8") (pinfunction "AGND_8") (pintype "bidirectional"))
    )
    (net (code "213") (name "unconnected-(U2-CAN1_RX-Pad20)") (class "Default")
      (node (ref "U2") (pin "20") (pinfunction "CAN1_RX_20") (pintype "bidirectional"))
    )
    (net (code "214") (name "unconnected-(U2-CAN1_TX-Pad22)") (class "Default")
      (node (ref "U2") (pin "22") (pinfunction "CAN1_TX_22") (pintype "bidirectional"))
    )
    (net (code "215") (name "unconnected-(U2-ERX_JM-Pad44)") (class "Default")
      (node (ref "U2") (pin "44") (pinfunction "ERX_JM_44") (pintype "bidirectional"))
    )
    (net (code "216") (name "unconnected-(U2-ERX_JP-Pad43)") (class "Default")
      (node (ref "U2") (pin "43") (pinfunction "ERX_JP_43") (pintype "bidirectional"))
    )
    (net (code "217") (name "unconnected-(U2-ETX_JM-Pad46)") (class "Default")
      (node (ref "U2") (pin "46") (pinfunction "ETX_JM_46") (pintype "bidirectional"))
    )
    (net (code "218") (name "unconnected-(U2-ETX_JP-Pad45)") (class "Default")
      (node (ref "U2") (pin "45") (pinfunction "ETX_JP_45") (pintype "bidirectional"))
    )
    (net (code "219") (name "unconnected-(U2-IRQ2-Pad50)") (class "Default")
      (node (ref "U2") (pin "50") (pinfunction "IRQ2_50") (pintype "bidirectional"))
    )
    (net (code "220") (name "unconnected-(U2-IRQ3-Pad49)") (class "Default")
      (node (ref "U2") (pin "49") (pinfunction "IRQ3_49") (pintype "bidirectional"))
    )
    (net (code "221") (name "unconnected-(U2-IRQ7-Pad9)") (class "Default")
      (node (ref "U2") (pin "9") (pinfunction "IRQ7_9") (pintype "bidirectional"))
    )
    (net (code "222") (name "unconnected-(U2-LINKLED-Pad42)") (class "Default")
      (node (ref "U2") (pin "42") (pinfunction "LINKLED_42") (pintype "bidirectional"))
    )
    (net (code "223") (name "unconnected-(U2-OW_DAT-Pad12)") (class "Default")
      (node (ref "U2") (pin "12") (pinfunction "OW_DAT_12") (pintype "bidirectional"))
    )
    (net (code "224") (name "unconnected-(U2-RSTI-Pad11)") (class "Default")
      (node (ref "U2") (pin "11") (pinfunction "RSTI_11") (pintype "bidirectional"))
    )
    (net (code "225") (name "unconnected-(U2-SDHC_DAT3-Pad15)") (class "Default")
      (node (ref "U2") (pin "15") (pinfunction "SDHC_DAT3_15") (pintype "bidirectional"))
    )
    (net (code "226") (name "unconnected-(U2-SPEEDLED-Pad40)") (class "Default")
      (node (ref "U2") (pin "40") (pinfunction "SPEEDLED_40") (pintype "bidirectional"))
    )
    (net (code "227") (name "unconnected-(U2-T0IN-Pad19)") (class "Default")
      (node (ref "U2") (pin "19") (pinfunction "T0IN_19") (pintype "bidirectional"))
    )
    (net (code "228") (name "unconnected-(U2-T1IN-Pad21)") (class "Default")
      (node (ref "U2") (pin "21") (pinfunction "T1IN_21") (pintype "bidirectional"))
    )
    (net (code "229") (name "unconnected-(U2-T3IN-Pad25)") (class "Default")
      (node (ref "U2") (pin "25") (pinfunction "T3IN_25") (pintype "bidirectional"))
    )
    (net (code "230") (name "unconnected-(U2-UART0_CTS-Pad30)") (class "Default")
      (node (ref "U2") (pin "30") (pinfunction "UART0_CTS_30") (pintype "bidirectional"))
    )
    (net (code "231") (name "unconnected-(U2-UART0_RTS-Pad28)") (class "Default")
      (node (ref "U2") (pin "28") (pinfunction "UART0_RTS_28") (pintype "bidirectional"))
    )
    (net (code "232") (name "unconnected-(U2-UART2_CTS-Pad10)") (class "Default")
      (node (ref "U2") (pin "10") (pinfunction "UART2_CTS_10") (pintype "bidirectional"))
    )
    (net (code "233") (name "unconnected-(U2-UART2_RTS-Pad14)") (class "Default")
      (node (ref "U2") (pin "14") (pinfunction "UART2_RTS_14") (pintype "bidirectional"))
    )
    (net (code "234") (name "unconnected-(U2-UART2_RX-Pad13)") (class "Default")
      (node (ref "U2") (pin "13") (pinfunction "UART2_RX_13") (pintype "bidirectional"))
    )
    (net (code "235") (name "unconnected-(U2-UART2_TX-Pad16)") (class "Default")
      (node (ref "U2") (pin "16") (pinfunction "UART2_TX_16") (pintype "bidirectional"))
    )
    (net (code "236") (name "unconnected-(U2-USBO_DM-Pad51)") (class "Default")
      (node (ref "U2") (pin "51") (pinfunction "USBO_DM_51") (pintype "bidirectional"))
    )
    (net (code "237") (name "unconnected-(U2-USBO_DP-Pad52)") (class "Default")
      (node (ref "U2") (pin "52") (pinfunction "USBO_DP_52") (pintype "bidirectional"))
    )
    (net (code "238") (name "unconnected-(U2-VCC3VE-Pad41)") (class "Default")
      (node (ref "U2") (pin "41") (pinfunction "VCC3VE_41") (pintype "bidirectional"))
    )
    (net (code "239") (name "unconnected-(U2-VDDA_DAC_ADC-Pad7)") (class "Default")
      (node (ref "U2") (pin "7") (pinfunction "VDDA_DAC_ADC_7") (pintype "bidirectional"))
    )
    (net (code "240") (name "unconnected-(U3-TIMER1-Pad2)") (class "Default")
      (node (ref "U3") (pin "2") (pinfunction "TIMER1_2") (pintype "bidirectional"))
    )
    (net (code "241") (name "unconnected-(U3-TIMER2-Pad4)") (class "Default")
      (node (ref "U3") (pin "4") (pinfunction "TIMER2_4") (pintype "bidirectional"))
    )
    (net (code "242") (name "unconnected-(U3-TIMER3-Pad6)") (class "Default")
      (node (ref "U3") (pin "6") (pinfunction "TIMER3_6") (pintype "bidirectional"))
    )
    (net (code "243") (name "unconnected-(U3-TIMER4-Pad8)") (class "Default")
      (node (ref "U3") (pin "8") (pinfunction "TIMER4_8") (pintype "bidirectional"))
    )
    (net (code "244") (name "unconnected-(U4-TIMER1-Pad2)") (class "Default")
      (node (ref "U4") (pin "2") (pinfunction "TIMER1_2") (pintype "bidirectional"))
    )
    (net (code "245") (name "unconnected-(U4-TIMER2-Pad4)") (class "Default")
      (node (ref "U4") (pin "4") (pinfunction "TIMER2_4") (pintype "bidirectional"))
    )
    (net (code "246") (name "unconnected-(U4-TIMER3-Pad6)") (class "Default")
      (node (ref "U4") (pin "6") (pinfunction "TIMER3_6") (pintype "bidirectional"))
    )
    (net (code "247") (name "unconnected-(U4-TIMER4-Pad8)") (class "Default")
      (node (ref "U4") (pin "8") (pinfunction "TIMER4_8") (pintype "bidirectional"))
    )
  )
)
